# BFMC_Powerboard_v0_2.net
KiCad netlist of a schematic drawn in EAGLE
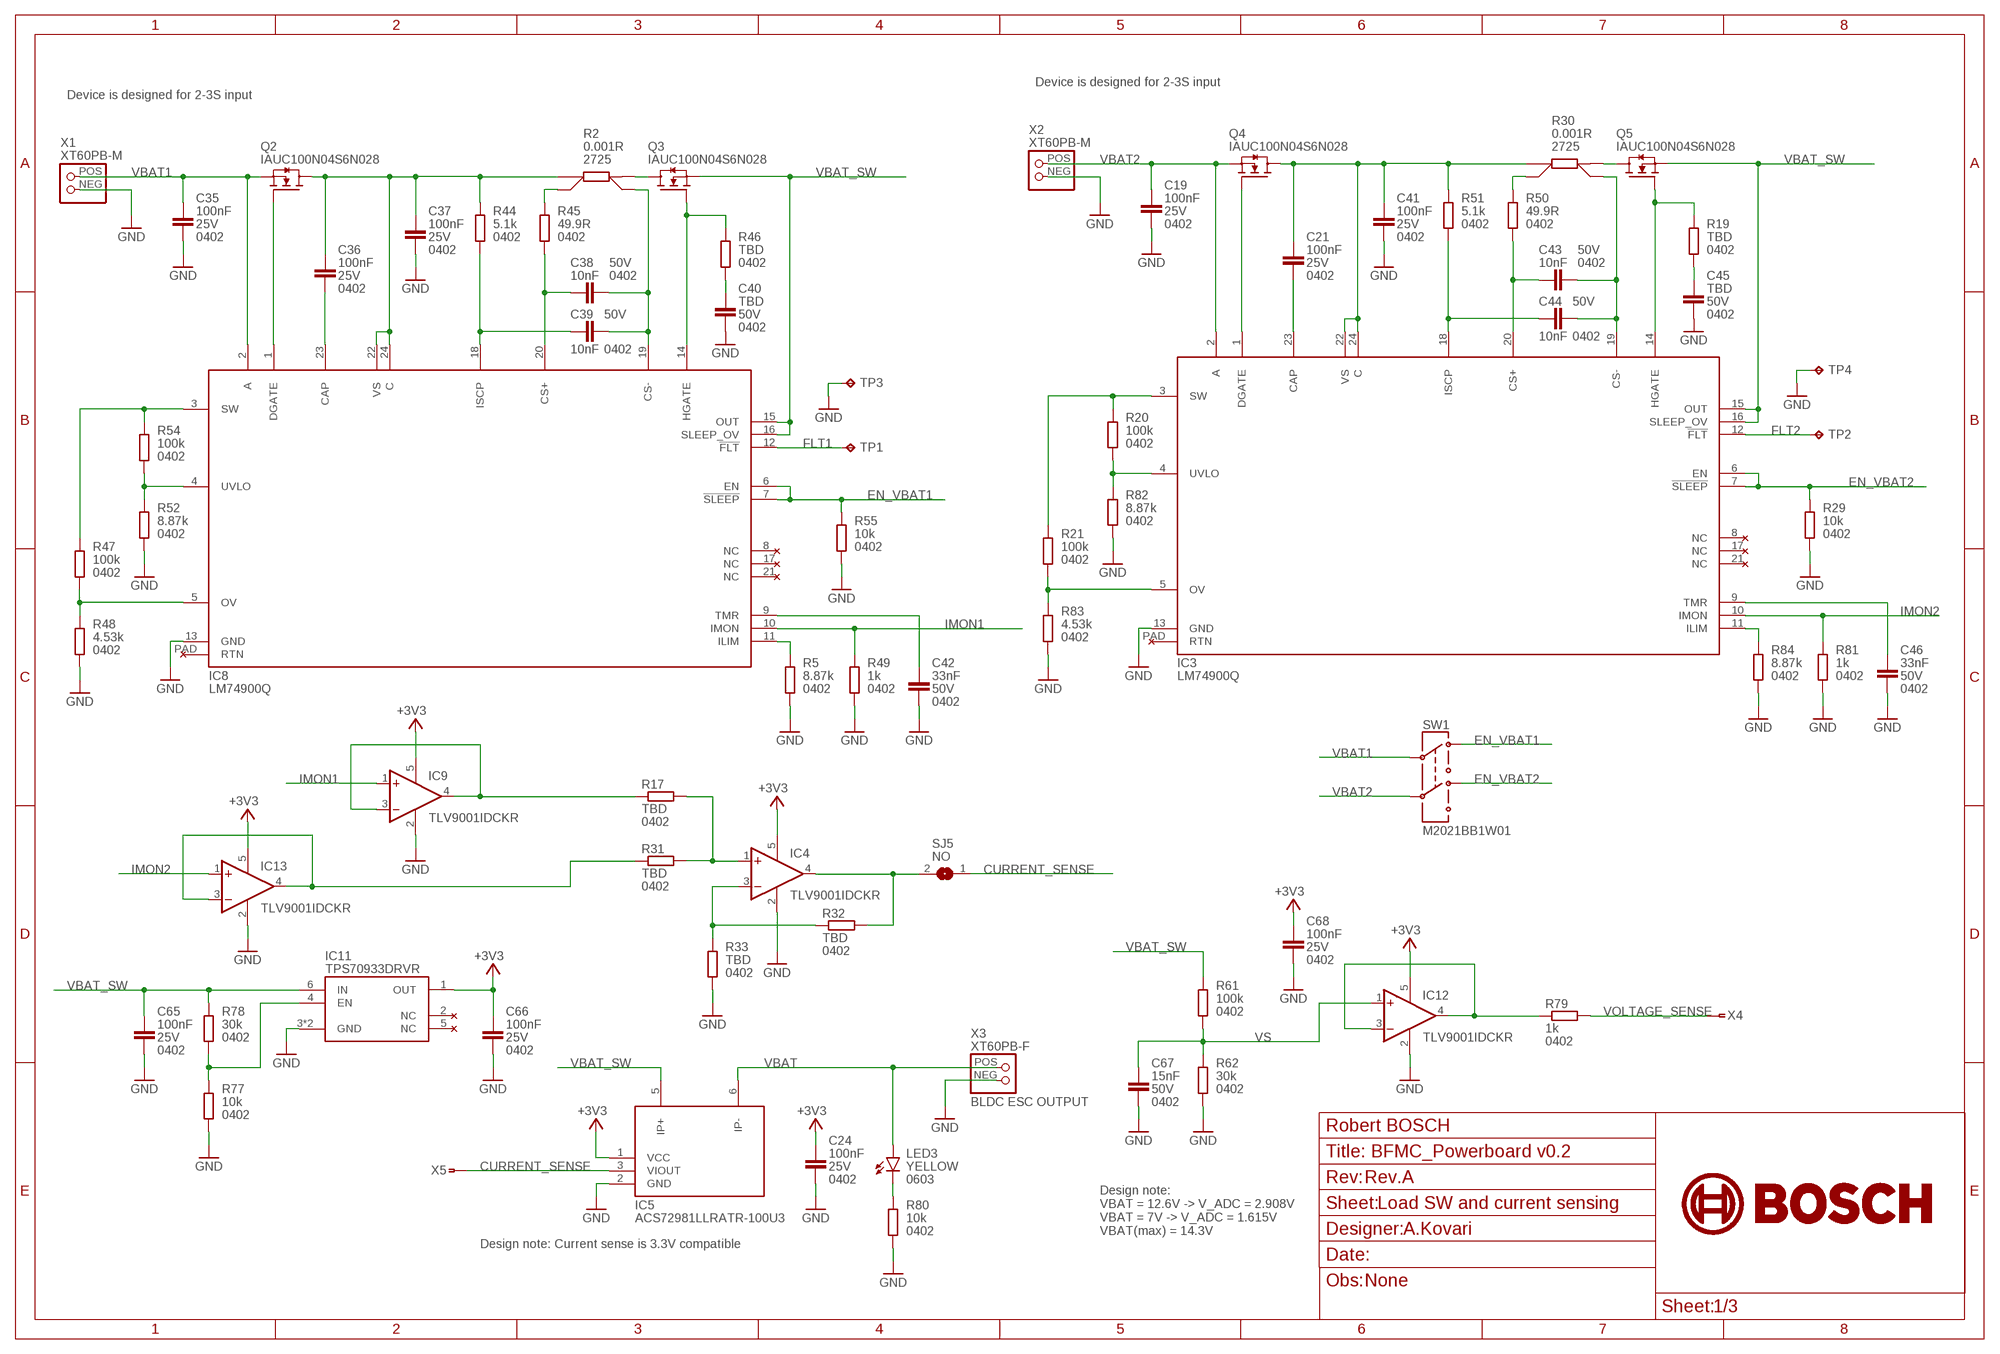
[diagram p0: schematic, sheet 1]
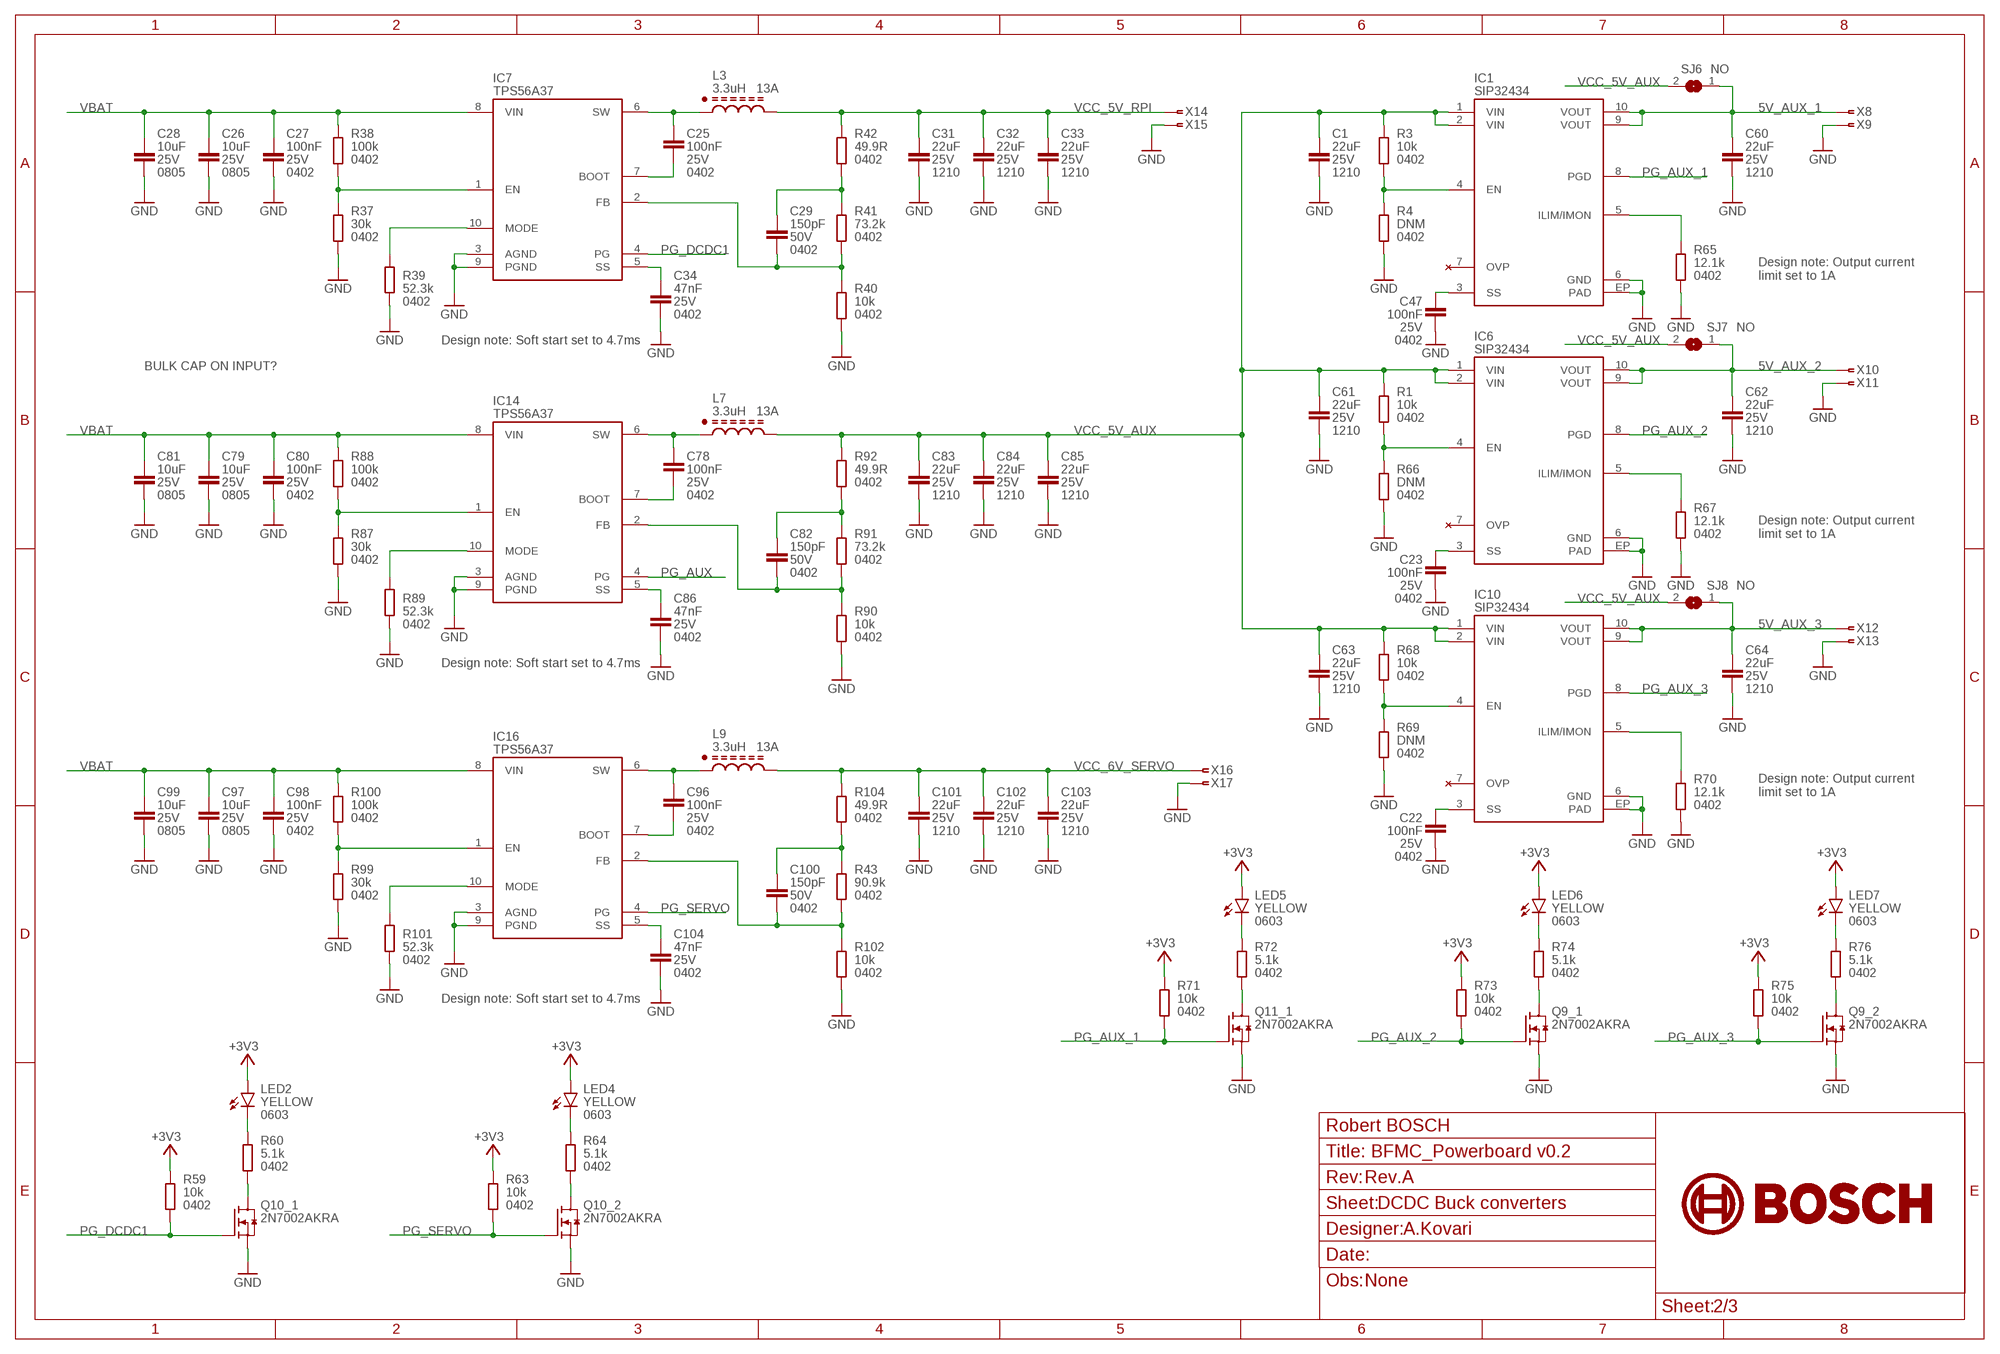
[diagram p1: schematic, sheet 2]
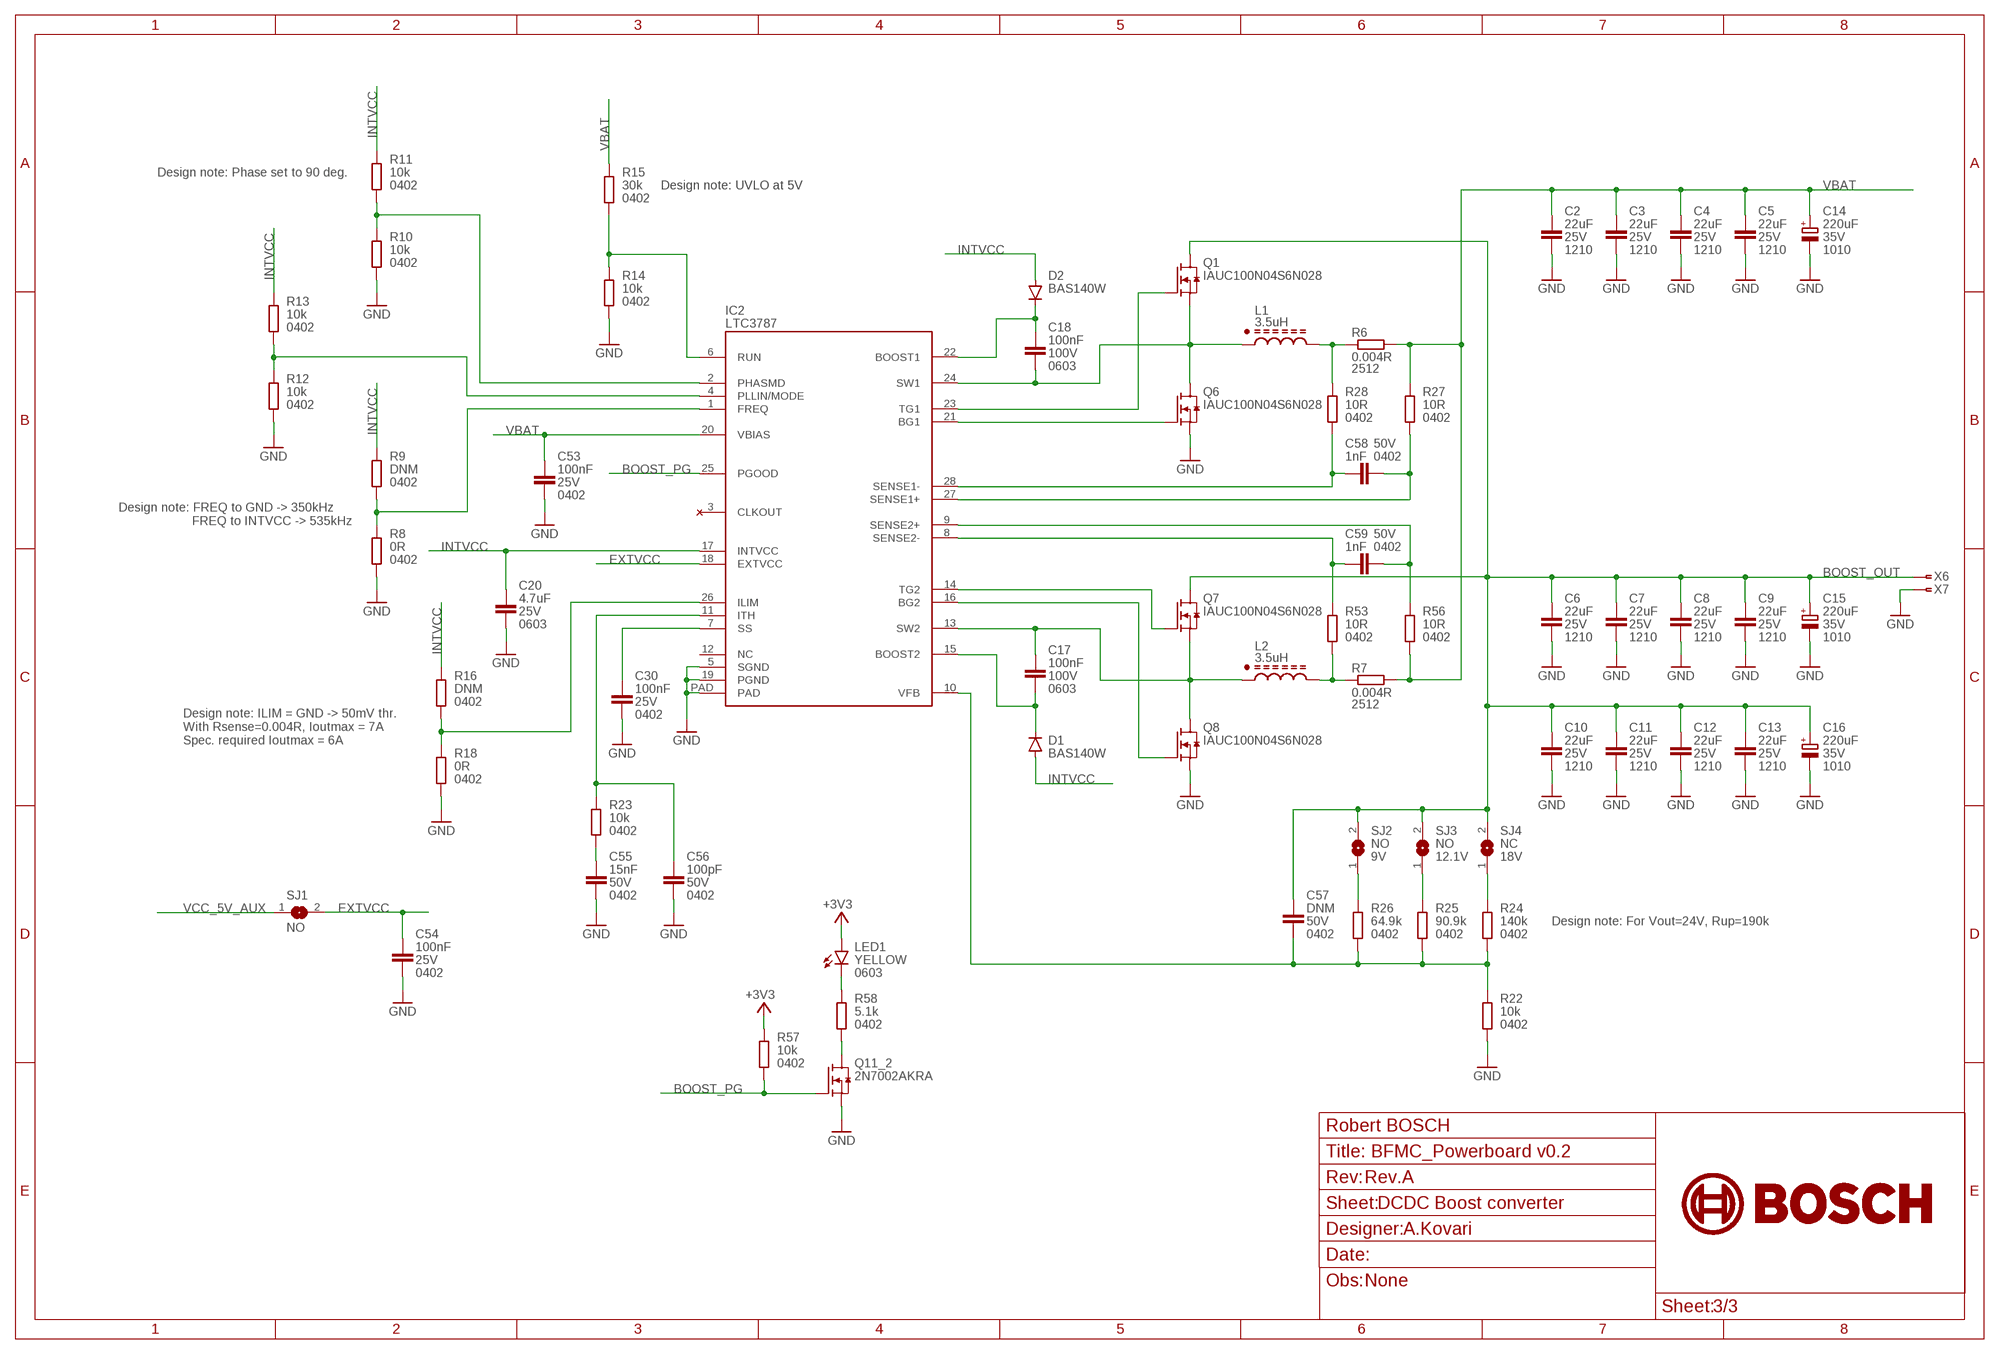
[diagram p2: schematic, sheet 3]

(export (version "E")
  (design (tool "Eeschema 10.0.6"))
  (components
    (comp (ref "C19")
      (value "100nF")
      (footprint "eagle-import:C0402_IPC")
      (fields
        (field (name "VOLTAGE") "25V")
        (field (name "PACKAGE") "0402")
        (field (name "MPN") "CL05B104KA5NNNC")
      )
      (libsource (lib "eagle-import") (part "CL05B104KA5NNNC"))
    )
    (comp (ref "C21")
      (value "100nF")
      (footprint "eagle-import:C0402_IPC")
      (fields
        (field (name "VOLTAGE") "25V")
        (field (name "PACKAGE") "0402")
        (field (name "MPN") "CL05B104KA5NNNC")
      )
      (libsource (lib "eagle-import") (part "CL05B104KA5NNNC"))
    )
    (comp (ref "C24")
      (value "100nF")
      (footprint "eagle-import:C0402_IPC")
      (fields
        (field (name "VOLTAGE") "25V")
        (field (name "PACKAGE") "0402")
        (field (name "MPN") "CL05B104KA5NNNC")
      )
      (libsource (lib "eagle-import") (part "CL05B104KA5NNNC"))
    )
    (comp (ref "C35")
      (value "100nF")
      (footprint "eagle-import:C0402_IPC")
      (fields
        (field (name "VOLTAGE") "25V")
        (field (name "PACKAGE") "0402")
        (field (name "MPN") "CL05B104KA5NNNC")
      )
      (libsource (lib "eagle-import") (part "CL05B104KA5NNNC"))
    )
    (comp (ref "C36")
      (value "100nF")
      (footprint "eagle-import:C0402_IPC")
      (fields
        (field (name "VOLTAGE") "25V")
        (field (name "PACKAGE") "0402")
        (field (name "MPN") "CL05B104KA5NNNC")
      )
      (libsource (lib "eagle-import") (part "CL05B104KA5NNNC"))
    )
    (comp (ref "C37")
      (value "100nF")
      (footprint "eagle-import:C0402_IPC")
      (fields
        (field (name "VOLTAGE") "25V")
        (field (name "PACKAGE") "0402")
        (field (name "MPN") "CL05B104KA5NNNC")
      )
      (libsource (lib "eagle-import") (part "CL05B104KA5NNNC"))
    )
    (comp (ref "C38")
      (value "10nF")
      (footprint "eagle-import:C0402_IPC")
      (fields
        (field (name "VOLTAGE") "50V")
        (field (name "PACKAGE") "0402")
        (field (name "MPN") "GCM155R71H103KA55D")
      )
      (libsource (lib "eagle-import") (part "GCM155R71H103KA55D"))
    )
    (comp (ref "C39")
      (value "10nF")
      (footprint "eagle-import:C0402_IPC")
      (fields
        (field (name "VOLTAGE") "50V")
        (field (name "PACKAGE") "0402")
        (field (name "MPN") "GCM155R71H103KA55D")
      )
      (libsource (lib "eagle-import") (part "GCM155R71H103KA55D"))
    )
    (comp (ref "C40")
      (value "TBD")
      (footprint "eagle-import:C0402_IPC")
      (fields
        (field (name "VOLTAGE") "50V")
        (field (name "PACKAGE") "0402")
        (field (name "MPN") "GCM155R71H103KA55D")
      )
      (libsource (lib "eagle-import") (part "GCM155R71H103KA55D"))
    )
    (comp (ref "C41")
      (value "100nF")
      (footprint "eagle-import:C0402_IPC")
      (fields
        (field (name "VOLTAGE") "25V")
        (field (name "PACKAGE") "0402")
        (field (name "MPN") "CL05B104KA5NNNC")
      )
      (libsource (lib "eagle-import") (part "CL05B104KA5NNNC"))
    )
    (comp (ref "C42")
      (value "33nF")
      (footprint "eagle-import:C0402_IPC")
      (fields
        (field (name "VOLTAGE") "50V")
        (field (name "PACKAGE") "0402")
        (field (name "MPN") "CGA2B3X7R1H333K050BB")
      )
      (libsource (lib "eagle-import") (part "CGA2B3X7R1H333K050BB"))
    )
    (comp (ref "C43")
      (value "10nF")
      (footprint "eagle-import:C0402_IPC")
      (fields
        (field (name "VOLTAGE") "50V")
        (field (name "PACKAGE") "0402")
        (field (name "MPN") "GCM155R71H103KA55D")
      )
      (libsource (lib "eagle-import") (part "GCM155R71H103KA55D"))
    )
    (comp (ref "C44")
      (value "10nF")
      (footprint "eagle-import:C0402_IPC")
      (fields
        (field (name "VOLTAGE") "50V")
        (field (name "PACKAGE") "0402")
        (field (name "MPN") "GCM155R71H103KA55D")
      )
      (libsource (lib "eagle-import") (part "GCM155R71H103KA55D"))
    )
    (comp (ref "C45")
      (value "TBD")
      (footprint "eagle-import:C0402_IPC")
      (fields
        (field (name "VOLTAGE") "50V")
        (field (name "PACKAGE") "0402")
        (field (name "MPN") "GCM155R71H103KA55D")
      )
      (libsource (lib "eagle-import") (part "GCM155R71H103KA55D"))
    )
    (comp (ref "C46")
      (value "33nF")
      (footprint "eagle-import:C0402_IPC")
      (fields
        (field (name "VOLTAGE") "50V")
        (field (name "PACKAGE") "0402")
        (field (name "MPN") "CGA2B3X7R1H333K050BB")
      )
      (libsource (lib "eagle-import") (part "CGA2B3X7R1H333K050BB"))
    )
    (comp (ref "C65")
      (value "100nF")
      (footprint "eagle-import:C0402_IPC")
      (fields
        (field (name "VOLTAGE") "25V")
        (field (name "PACKAGE") "0402")
        (field (name "MPN") "CL05B104KA5NNNC")
      )
      (libsource (lib "eagle-import") (part "CL05B104KA5NNNC"))
    )
    (comp (ref "C66")
      (value "100nF")
      (footprint "eagle-import:C0402_IPC")
      (fields
        (field (name "VOLTAGE") "25V")
        (field (name "PACKAGE") "0402")
        (field (name "MPN") "CL05B104KA5NNNC")
      )
      (libsource (lib "eagle-import") (part "CL05B104KA5NNNC"))
    )
    (comp (ref "C67")
      (value "15nF")
      (footprint "eagle-import:C0402_IPC")
      (fields
        (field (name "VOLTAGE") "50V")
        (field (name "PACKAGE") "0402")
        (field (name "MPN") "GRM155R71H153KA12J")
      )
      (libsource (lib "eagle-import") (part "GRM155R71H153KA12J"))
    )
    (comp (ref "C68")
      (value "100nF")
      (footprint "eagle-import:C0402_IPC")
      (fields
        (field (name "VOLTAGE") "25V")
        (field (name "PACKAGE") "0402")
        (field (name "MPN") "CL05B104KA5NNNC")
      )
      (libsource (lib "eagle-import") (part "CL05B104KA5NNNC"))
    )
    (comp (ref "IC3")
      (value "LM74900Q")
      (footprint "eagle-import:QFN24-4X4")
      (fields (field (name "MPN") " LM74900QRGERQ1"))
      (libsource (lib "eagle-import") (part "LM74900Q"))
    )
    (comp (ref "IC4")
      (value "TLV9001IDCKR")
      (footprint "eagle-import:SC70-5")
      (fields (field (name "MPN") "TLV9001SIDCKR "))
      (libsource (lib "eagle-import") (part "TLV9001IDCKR"))
    )
    (comp (ref "IC5")
      (value "ACS72981LLRATR-100U3")
      (footprint "eagle-import:ACS72981")
      (libsource (lib "eagle-import") (part "ACS72981LLRATR-100U3"))
    )
    (comp (ref "IC8")
      (value "LM74900Q")
      (footprint "eagle-import:QFN24-4X4")
      (fields (field (name "MPN") " LM74900QRGERQ1"))
      (libsource (lib "eagle-import") (part "LM74900Q"))
    )
    (comp (ref "IC9")
      (value "TLV9001IDCKR")
      (footprint "eagle-import:SC70-5")
      (fields (field (name "MPN") "TLV9001SIDCKR "))
      (libsource (lib "eagle-import") (part "TLV9001IDCKR"))
    )
    (comp (ref "IC11")
      (value "TPS70933DRVR")
      (footprint "eagle-import:WSON6_2X2MM_NO_SILK")
      (libsource (lib "eagle-import") (part "TPS70933DRVR"))
    )
    (comp (ref "IC12")
      (value "TLV9001IDCKR")
      (footprint "eagle-import:SC70-5")
      (fields (field (name "MPN") "TLV9001SIDCKR "))
      (libsource (lib "eagle-import") (part "TLV9001IDCKR"))
    )
    (comp (ref "IC13")
      (value "TLV9001IDCKR")
      (footprint "eagle-import:SC70-5")
      (fields (field (name "MPN") "TLV9001SIDCKR "))
      (libsource (lib "eagle-import") (part "TLV9001IDCKR"))
    )
    (comp (ref "LED3")
      (value "YELLOW")
      (footprint "eagle-import:CHIPLED_0603")
      (fields (field (name "PACKAGE") "0603") (field (name "MPN") "150060YS75000"))
      (libsource (lib "eagle-import") (part "150060YS75000"))
    )
    (comp (ref "Q2")
      (value "IAUC100N04S6N028")
      (footprint "eagle-import:PG-TDSON-8")
      (fields (field (name "MPN") " IAUC100N04S6N028"))
      (libsource (lib "eagle-import") (part "IAUC100N04S6N028ATMA1"))
    )
    (comp (ref "Q3")
      (value "IAUC100N04S6N028")
      (footprint "eagle-import:PG-TDSON-8")
      (fields (field (name "MPN") " IAUC100N04S6N028"))
      (libsource (lib "eagle-import") (part "IAUC100N04S6N028ATMA1"))
    )
    (comp (ref "Q4")
      (value "IAUC100N04S6N028")
      (footprint "eagle-import:PG-TDSON-8")
      (fields (field (name "MPN") " IAUC100N04S6N028"))
      (libsource (lib "eagle-import") (part "IAUC100N04S6N028ATMA1"))
    )
    (comp (ref "Q5")
      (value "IAUC100N04S6N028")
      (footprint "eagle-import:PG-TDSON-8")
      (fields (field (name "MPN") " IAUC100N04S6N028"))
      (libsource (lib "eagle-import") (part "IAUC100N04S6N028ATMA1"))
    )
    (comp (ref "R2")
      (value "0.001R")
      (footprint "eagle-import:CRS272")
      (fields (field (name "MPN") "CST272FK-13-R001AA ") (field (name "PACKAGE") "2725"))
      (libsource (lib "eagle-import") (part "CST272FK-13-R001AA"))
    )
    (comp (ref "R5")
      (value "8.87k")
      (footprint "eagle-import:R0402_IPC")
      (fields (field (name "PACKAGE") "0402") (field (name "MPN") "RC0402FR-078K87L"))
      (libsource (lib "eagle-import") (part "RC0402FR-078K87L"))
    )
    (comp (ref "R17")
      (value "TBD")
      (footprint "eagle-import:R0402_IPC")
      (fields (field (name "PACKAGE") "0402") (field (name "MPN") "RC0402FR-131KL"))
      (libsource (lib "eagle-import") (part "RC0402FR-131KL"))
    )
    (comp (ref "R19")
      (value "TBD")
      (footprint "eagle-import:R0402_IPC")
      (fields (field (name "PACKAGE") "0402") (field (name "MPN") "RC0402FR-1349R9L"))
      (libsource (lib "eagle-import") (part "RC0402FR-1349R9L"))
    )
    (comp (ref "R20")
      (value "100k")
      (footprint "eagle-import:R0402_IPC")
      (fields (field (name "PACKAGE") "0402") (field (name "MPN") "RC0402FR-13100KL"))
      (libsource (lib "eagle-import") (part "RC0402FR-13100KL"))
    )
    (comp (ref "R21")
      (value "100k")
      (footprint "eagle-import:R0402_IPC")
      (fields (field (name "PACKAGE") "0402") (field (name "MPN") "RC0402FR-13100KL"))
      (libsource (lib "eagle-import") (part "RC0402FR-13100KL"))
    )
    (comp (ref "R29")
      (value "10k")
      (footprint "eagle-import:R0402_IPC")
      (fields (field (name "PACKAGE") "0402") (field (name "MPN") "RC0402FR-1310KL"))
      (libsource (lib "eagle-import") (part "RC0402FR-1310KL"))
    )
    (comp (ref "R30")
      (value "0.001R")
      (footprint "eagle-import:CRS272")
      (fields (field (name "MPN") "CST272FK-13-R001AA ") (field (name "PACKAGE") "2725"))
      (libsource (lib "eagle-import") (part "CST272FK-13-R001AA"))
    )
    (comp (ref "R31")
      (value "TBD")
      (footprint "eagle-import:R0402_IPC")
      (fields (field (name "PACKAGE") "0402") (field (name "MPN") "RC0402FR-131KL"))
      (libsource (lib "eagle-import") (part "RC0402FR-131KL"))
    )
    (comp (ref "R32")
      (value "TBD")
      (footprint "eagle-import:R0402_IPC")
      (fields (field (name "PACKAGE") "0402") (field (name "MPN") "RC0402FR-131KL"))
      (libsource (lib "eagle-import") (part "RC0402FR-131KL"))
    )
    (comp (ref "R33")
      (value "TBD")
      (footprint "eagle-import:R0402_IPC")
      (fields (field (name "PACKAGE") "0402") (field (name "MPN") "RC0402FR-131KL"))
      (libsource (lib "eagle-import") (part "RC0402FR-131KL"))
    )
    (comp (ref "R44")
      (value "5.1k")
      (footprint "eagle-import:R0402_IPC")
      (fields (field (name "PACKAGE") "0402") (field (name "MPN") "RC0402FR-135K1L"))
      (libsource (lib "eagle-import") (part "RC0402FR-135K1L"))
    )
    (comp (ref "R45")
      (value "49.9R")
      (footprint "eagle-import:R0402_IPC")
      (fields (field (name "PACKAGE") "0402") (field (name "MPN") "RC0402FR-1349R9L"))
      (libsource (lib "eagle-import") (part "RC0402FR-1349R9L"))
    )
    (comp (ref "R46")
      (value "TBD")
      (footprint "eagle-import:R0402_IPC")
      (fields (field (name "PACKAGE") "0402") (field (name "MPN") "RC0402FR-1349R9L"))
      (libsource (lib "eagle-import") (part "RC0402FR-1349R9L"))
    )
    (comp (ref "R47")
      (value "100k")
      (footprint "eagle-import:R0402_IPC")
      (fields (field (name "PACKAGE") "0402") (field (name "MPN") "RC0402FR-13100KL"))
      (libsource (lib "eagle-import") (part "RC0402FR-13100KL"))
    )
    (comp (ref "R48")
      (value "4.53k")
      (footprint "eagle-import:R0402_IPC")
      (fields (field (name "PACKAGE") "0402") (field (name "MPN") "RC0402FR-074K53L"))
      (libsource (lib "eagle-import") (part "RC0402FR-074K53L"))
    )
    (comp (ref "R49")
      (value "1k")
      (footprint "eagle-import:R0402_IPC")
      (fields (field (name "PACKAGE") "0402") (field (name "MPN") "RC0402FR-131KL"))
      (libsource (lib "eagle-import") (part "RC0402FR-131KL"))
    )
    (comp (ref "R50")
      (value "49.9R")
      (footprint "eagle-import:R0402_IPC")
      (fields (field (name "PACKAGE") "0402") (field (name "MPN") "RC0402FR-1349R9L"))
      (libsource (lib "eagle-import") (part "RC0402FR-1349R9L"))
    )
    (comp (ref "R51")
      (value "5.1k")
      (footprint "eagle-import:R0402_IPC")
      (fields (field (name "PACKAGE") "0402") (field (name "MPN") "RC0402FR-135K1L"))
      (libsource (lib "eagle-import") (part "RC0402FR-135K1L"))
    )
    (comp (ref "R52")
      (value "8.87k")
      (footprint "eagle-import:R0402_IPC")
      (fields (field (name "PACKAGE") "0402") (field (name "MPN") "RC0402FR-078K87L"))
      (libsource (lib "eagle-import") (part "RC0402FR-078K87L"))
    )
    (comp (ref "R54")
      (value "100k")
      (footprint "eagle-import:R0402_IPC")
      (fields (field (name "PACKAGE") "0402") (field (name "MPN") "RC0402FR-13100KL"))
      (libsource (lib "eagle-import") (part "RC0402FR-13100KL"))
    )
    (comp (ref "R55")
      (value "10k")
      (footprint "eagle-import:R0402_IPC")
      (fields (field (name "PACKAGE") "0402") (field (name "MPN") "RC0402FR-1310KL"))
      (libsource (lib "eagle-import") (part "RC0402FR-1310KL"))
    )
    (comp (ref "R61")
      (value "100k")
      (footprint "eagle-import:R0402_IPC")
      (fields (field (name "PACKAGE") "0402") (field (name "MPN") "RC0402FR-13100KL"))
      (libsource (lib "eagle-import") (part "RC0402FR-13100KL"))
    )
    (comp (ref "R62")
      (value "30k")
      (footprint "eagle-import:R0402_IPC")
      (fields (field (name "PACKAGE") "0402") (field (name "MPN") "RC0402FR-1330KL"))
      (libsource (lib "eagle-import") (part "RC0402FR-1330KL"))
    )
    (comp (ref "R77")
      (value "10k")
      (footprint "eagle-import:R0402_IPC")
      (fields (field (name "PACKAGE") "0402") (field (name "MPN") "RC0402FR-1310KL"))
      (libsource (lib "eagle-import") (part "RC0402FR-1310KL"))
    )
    (comp (ref "R78")
      (value "30k")
      (footprint "eagle-import:R0402_IPC")
      (fields (field (name "PACKAGE") "0402") (field (name "MPN") "RC0402FR-1330KL"))
      (libsource (lib "eagle-import") (part "RC0402FR-1330KL"))
    )
    (comp (ref "R79")
      (value "1k")
      (footprint "eagle-import:R0402_IPC")
      (fields (field (name "PACKAGE") "0402") (field (name "MPN") "RC0402FR-131KL"))
      (libsource (lib "eagle-import") (part "RC0402FR-131KL"))
    )
    (comp (ref "R80")
      (value "10k")
      (footprint "eagle-import:R0402_IPC")
      (fields (field (name "PACKAGE") "0402") (field (name "MPN") "RC0402FR-1310KL"))
      (libsource (lib "eagle-import") (part "RC0402FR-1310KL"))
    )
    (comp (ref "R81")
      (value "1k")
      (footprint "eagle-import:R0402_IPC")
      (fields (field (name "PACKAGE") "0402") (field (name "MPN") "RC0402FR-131KL"))
      (libsource (lib "eagle-import") (part "RC0402FR-131KL"))
    )
    (comp (ref "R82")
      (value "8.87k")
      (footprint "eagle-import:R0402_IPC")
      (fields (field (name "PACKAGE") "0402") (field (name "MPN") "RC0402FR-078K87L"))
      (libsource (lib "eagle-import") (part "RC0402FR-078K87L"))
    )
    (comp (ref "R83")
      (value "4.53k")
      (footprint "eagle-import:R0402_IPC")
      (fields (field (name "PACKAGE") "0402") (field (name "MPN") "RC0402FR-074K53L"))
      (libsource (lib "eagle-import") (part "RC0402FR-074K53L"))
    )
    (comp (ref "R84")
      (value "8.87k")
      (footprint "eagle-import:R0402_IPC")
      (fields (field (name "PACKAGE") "0402") (field (name "MPN") "RC0402FR-078K87L"))
      (libsource (lib "eagle-import") (part "RC0402FR-078K87L"))
    )
    (comp (ref "SJ5")
      (value "NO")
      (footprint "eagle-import:SJ_1X1.5_NO")
      (libsource (lib "eagle-import") (part "SJ_1.5X1_NO"))
    )
    (comp (ref "SW1")
      (value "M2021BB1W01")
      (footprint "eagle-import:M2021BB1W01")
      (libsource (lib "eagle-import") (part "M2021BB1W01"))
    )
    (comp (ref "TP1")
      (value "TPTP13R")
      (footprint "eagle-import:TP13R")
      (libsource (lib "eagle-import") (part "TPTP13R"))
    )
    (comp (ref "TP2")
      (value "TPTP13R")
      (footprint "eagle-import:TP13R")
      (libsource (lib "eagle-import") (part "TPTP13R"))
    )
    (comp (ref "TP3")
      (value "TPTP13R")
      (footprint "eagle-import:TP13R")
      (libsource (lib "eagle-import") (part "TPTP13R"))
    )
    (comp (ref "TP4")
      (value "TPTP13R")
      (footprint "eagle-import:TP13R")
      (libsource (lib "eagle-import") (part "TPTP13R"))
    )
    (comp (ref "X1")
      (value "XT60PB-M")
      (footprint "eagle-import:XT60PB")
      (libsource (lib "eagle-import") (part "XT60PB-M"))
    )
    (comp (ref "X2")
      (value "XT60PB-M")
      (footprint "eagle-import:XT60PB")
      (libsource (lib "eagle-import") (part "XT60PB-M"))
    )
    (comp (ref "X3")
      (value "XT60PB-F")
      (footprint "eagle-import:XT60PB")
      (libsource (lib "eagle-import") (part "XT60PB-F"))
    )
    (comp (ref "X4")
      (value "ZFKDSA1-W-6,35")
      (footprint "eagle-import:1704994")
      (fields (field (name "MPN") "1704994"))
      (libsource (lib "eagle-import") (part "ZFKDSA1-W-6,35"))
    )
    (comp (ref "X5")
      (value "ZFKDSA1-W-6,35")
      (footprint "eagle-import:1704994")
      (fields (field (name "MPN") "1704994"))
      (libsource (lib "eagle-import") (part "ZFKDSA1-W-6,35"))
    )
    (comp (ref "C1")
      (value "22uF")
      (footprint "eagle-import:C1210")
      (fields
        (field (name "PACKAGE") "1210")
        (field (name "VOLTAGE") "25V")
        (field (name "MPN") "CL32A226KAJNNNE")
      )
      (libsource (lib "eagle-import") (part "CL32A226KAJNNNE"))
    )
    (comp (ref "C22")
      (value "100nF")
      (footprint "eagle-import:C0402_IPC")
      (fields
        (field (name "VOLTAGE") "25V")
        (field (name "PACKAGE") "0402")
        (field (name "MPN") "CL05B104KA5NNNC")
      )
      (libsource (lib "eagle-import") (part "CL05B104KA5NNNC"))
    )
    (comp (ref "C23")
      (value "100nF")
      (footprint "eagle-import:C0402_IPC")
      (fields
        (field (name "VOLTAGE") "25V")
        (field (name "PACKAGE") "0402")
        (field (name "MPN") "CL05B104KA5NNNC")
      )
      (libsource (lib "eagle-import") (part "CL05B104KA5NNNC"))
    )
    (comp (ref "C25")
      (value "100nF")
      (footprint "eagle-import:C0402_IPC")
      (fields
        (field (name "VOLTAGE") "25V")
        (field (name "PACKAGE") "0402")
        (field (name "MPN") "CL05B104KA5NNNC")
      )
      (libsource (lib "eagle-import") (part "CL05B104KA5NNNC"))
    )
    (comp (ref "C26")
      (value "10uF")
      (footprint "eagle-import:C0805")
      (fields
        (field (name "PACKAGE") "0805")
        (field (name "VOLTAGE") "25V")
        (field (name "MPN") "GRM21BR61E106KA73K")
      )
      (libsource (lib "eagle-import") (part "GRM21BR61E106KA73K"))
    )
    (comp (ref "C27")
      (value "100nF")
      (footprint "eagle-import:C0402_IPC")
      (fields
        (field (name "VOLTAGE") "25V")
        (field (name "PACKAGE") "0402")
        (field (name "MPN") "CL05B104KA5NNNC")
      )
      (libsource (lib "eagle-import") (part "CL05B104KA5NNNC"))
    )
    (comp (ref "C28")
      (value "10uF")
      (footprint "eagle-import:C0805")
      (fields
        (field (name "PACKAGE") "0805")
        (field (name "VOLTAGE") "25V")
        (field (name "MPN") "GRM21BR61E106KA73K")
      )
      (libsource (lib "eagle-import") (part "GRM21BR61E106KA73K"))
    )
    (comp (ref "C29")
      (value "150pF")
      (footprint "eagle-import:C0402_IPC")
      (fields
        (field (name "VOLTAGE") "50V")
        (field (name "PACKAGE") "0402")
        (field (name "MPN") "GCM1555C1H151JA16J")
      )
      (libsource (lib "eagle-import") (part "GCM1555C1H151JA16J"))
    )
    (comp (ref "C31")
      (value "22uF")
      (footprint "eagle-import:C1210")
      (fields
        (field (name "PACKAGE") "1210")
        (field (name "VOLTAGE") "25V")
        (field (name "MPN") "CL32A226KAJNNNE")
      )
      (libsource (lib "eagle-import") (part "CL32A226KAJNNNE"))
    )
    (comp (ref "C32")
      (value "22uF")
      (footprint "eagle-import:C1210")
      (fields
        (field (name "PACKAGE") "1210")
        (field (name "VOLTAGE") "25V")
        (field (name "MPN") "CL32A226KAJNNNE")
      )
      (libsource (lib "eagle-import") (part "CL32A226KAJNNNE"))
    )
    (comp (ref "C33")
      (value "22uF")
      (footprint "eagle-import:C1210")
      (fields
        (field (name "PACKAGE") "1210")
        (field (name "VOLTAGE") "25V")
        (field (name "MPN") "CL32A226KAJNNNE")
      )
      (libsource (lib "eagle-import") (part "CL32A226KAJNNNE"))
    )
    (comp (ref "C34")
      (value "47nF")
      (footprint "eagle-import:C0402_IPC")
      (fields
        (field (name "VOLTAGE") "25V")
        (field (name "PACKAGE") "0402")
        (field (name "MPN") "CL05B473KA5NNNC")
      )
      (libsource (lib "eagle-import") (part "CL05B473KA5NNNC"))
    )
    (comp (ref "C47")
      (value "100nF")
      (footprint "eagle-import:C0402_IPC")
      (fields
        (field (name "VOLTAGE") "25V")
        (field (name "PACKAGE") "0402")
        (field (name "MPN") "CL05B104KA5NNNC")
      )
      (libsource (lib "eagle-import") (part "CL05B104KA5NNNC"))
    )
    (comp (ref "C60")
      (value "22uF")
      (footprint "eagle-import:C1210")
      (fields
        (field (name "PACKAGE") "1210")
        (field (name "VOLTAGE") "25V")
        (field (name "MPN") "CL32A226KAJNNNE")
      )
      (libsource (lib "eagle-import") (part "CL32A226KAJNNNE"))
    )
    (comp (ref "C61")
      (value "22uF")
      (footprint "eagle-import:C1210")
      (fields
        (field (name "PACKAGE") "1210")
        (field (name "VOLTAGE") "25V")
        (field (name "MPN") "CL32A226KAJNNNE")
      )
      (libsource (lib "eagle-import") (part "CL32A226KAJNNNE"))
    )
    (comp (ref "C62")
      (value "22uF")
      (footprint "eagle-import:C1210")
      (fields
        (field (name "PACKAGE") "1210")
        (field (name "VOLTAGE") "25V")
        (field (name "MPN") "CL32A226KAJNNNE")
      )
      (libsource (lib "eagle-import") (part "CL32A226KAJNNNE"))
    )
    (comp (ref "C63")
      (value "22uF")
      (footprint "eagle-import:C1210")
      (fields
        (field (name "PACKAGE") "1210")
        (field (name "VOLTAGE") "25V")
        (field (name "MPN") "CL32A226KAJNNNE")
      )
      (libsource (lib "eagle-import") (part "CL32A226KAJNNNE"))
    )
    (comp (ref "C64")
      (value "22uF")
      (footprint "eagle-import:C1210")
      (fields
        (field (name "PACKAGE") "1210")
        (field (name "VOLTAGE") "25V")
        (field (name "MPN") "CL32A226KAJNNNE")
      )
      (libsource (lib "eagle-import") (part "CL32A226KAJNNNE"))
    )
    (comp (ref "C78")
      (value "100nF")
      (footprint "eagle-import:C0402_IPC")
      (fields
        (field (name "VOLTAGE") "25V")
        (field (name "PACKAGE") "0402")
        (field (name "MPN") "CL05B104KA5NNNC")
      )
      (libsource (lib "eagle-import") (part "CL05B104KA5NNNC"))
    )
    (comp (ref "C79")
      (value "10uF")
      (footprint "eagle-import:C0805")
      (fields
        (field (name "PACKAGE") "0805")
        (field (name "VOLTAGE") "25V")
        (field (name "MPN") "GRM21BR61E106KA73K")
      )
      (libsource (lib "eagle-import") (part "GRM21BR61E106KA73K"))
    )
    (comp (ref "C80")
      (value "100nF")
      (footprint "eagle-import:C0402_IPC")
      (fields
        (field (name "VOLTAGE") "25V")
        (field (name "PACKAGE") "0402")
        (field (name "MPN") "CL05B104KA5NNNC")
      )
      (libsource (lib "eagle-import") (part "CL05B104KA5NNNC"))
    )
    (comp (ref "C81")
      (value "10uF")
      (footprint "eagle-import:C0805")
      (fields
        (field (name "PACKAGE") "0805")
        (field (name "VOLTAGE") "25V")
        (field (name "MPN") "GRM21BR61E106KA73K")
      )
      (libsource (lib "eagle-import") (part "GRM21BR61E106KA73K"))
    )
    (comp (ref "C82")
      (value "150pF")
      (footprint "eagle-import:C0402_IPC")
      (fields
        (field (name "VOLTAGE") "50V")
        (field (name "PACKAGE") "0402")
        (field (name "MPN") "GCM1555C1H151JA16J")
      )
      (libsource (lib "eagle-import") (part "GCM1555C1H151JA16J"))
    )
    (comp (ref "C83")
      (value "22uF")
      (footprint "eagle-import:C1210")
      (fields
        (field (name "PACKAGE") "1210")
        (field (name "VOLTAGE") "25V")
        (field (name "MPN") "CL32A226KAJNNNE")
      )
      (libsource (lib "eagle-import") (part "CL32A226KAJNNNE"))
    )
    (comp (ref "C84")
      (value "22uF")
      (footprint "eagle-import:C1210")
      (fields
        (field (name "PACKAGE") "1210")
        (field (name "VOLTAGE") "25V")
        (field (name "MPN") "CL32A226KAJNNNE")
      )
      (libsource (lib "eagle-import") (part "CL32A226KAJNNNE"))
    )
    (comp (ref "C85")
      (value "22uF")
      (footprint "eagle-import:C1210")
      (fields
        (field (name "PACKAGE") "1210")
        (field (name "VOLTAGE") "25V")
        (field (name "MPN") "CL32A226KAJNNNE")
      )
      (libsource (lib "eagle-import") (part "CL32A226KAJNNNE"))
    )
    (comp (ref "C86")
      (value "47nF")
      (footprint "eagle-import:C0402_IPC")
      (fields
        (field (name "VOLTAGE") "25V")
        (field (name "PACKAGE") "0402")
        (field (name "MPN") "CL05B473KA5NNNC")
      )
      (libsource (lib "eagle-import") (part "CL05B473KA5NNNC"))
    )
    (comp (ref "C96")
      (value "100nF")
      (footprint "eagle-import:C0402_IPC")
      (fields
        (field (name "VOLTAGE") "25V")
        (field (name "PACKAGE") "0402")
        (field (name "MPN") "CL05B104KA5NNNC")
      )
      (libsource (lib "eagle-import") (part "CL05B104KA5NNNC"))
    )
    (comp (ref "C97")
      (value "10uF")
      (footprint "eagle-import:C0805")
      (fields
        (field (name "PACKAGE") "0805")
        (field (name "VOLTAGE") "25V")
        (field (name "MPN") "GRM21BR61E106KA73K")
      )
      (libsource (lib "eagle-import") (part "GRM21BR61E106KA73K"))
    )
    (comp (ref "C98")
      (value "100nF")
      (footprint "eagle-import:C0402_IPC")
      (fields
        (field (name "VOLTAGE") "25V")
        (field (name "PACKAGE") "0402")
        (field (name "MPN") "CL05B104KA5NNNC")
      )
      (libsource (lib "eagle-import") (part "CL05B104KA5NNNC"))
    )
    (comp (ref "C99")
      (value "10uF")
      (footprint "eagle-import:C0805")
      (fields
        (field (name "PACKAGE") "0805")
        (field (name "VOLTAGE") "25V")
        (field (name "MPN") "GRM21BR61E106KA73K")
      )
      (libsource (lib "eagle-import") (part "GRM21BR61E106KA73K"))
    )
    (comp (ref "C100")
      (value "150pF")
      (footprint "eagle-import:C0402_IPC")
      (fields
        (field (name "VOLTAGE") "50V")
        (field (name "PACKAGE") "0402")
        (field (name "MPN") "GCM1555C1H151JA16J")
      )
      (libsource (lib "eagle-import") (part "GCM1555C1H151JA16J"))
    )
    (comp (ref "C101")
      (value "22uF")
      (footprint "eagle-import:C1210")
      (fields
        (field (name "PACKAGE") "1210")
        (field (name "VOLTAGE") "25V")
        (field (name "MPN") "CL32A226KAJNNNE")
      )
      (libsource (lib "eagle-import") (part "CL32A226KAJNNNE"))
    )
    (comp (ref "C102")
      (value "22uF")
      (footprint "eagle-import:C1210")
      (fields
        (field (name "PACKAGE") "1210")
        (field (name "VOLTAGE") "25V")
        (field (name "MPN") "CL32A226KAJNNNE")
      )
      (libsource (lib "eagle-import") (part "CL32A226KAJNNNE"))
    )
    (comp (ref "C103")
      (value "22uF")
      (footprint "eagle-import:C1210")
      (fields
        (field (name "PACKAGE") "1210")
        (field (name "VOLTAGE") "25V")
        (field (name "MPN") "CL32A226KAJNNNE")
      )
      (libsource (lib "eagle-import") (part "CL32A226KAJNNNE"))
    )
    (comp (ref "C104")
      (value "47nF")
      (footprint "eagle-import:C0402_IPC")
      (fields
        (field (name "VOLTAGE") "25V")
        (field (name "PACKAGE") "0402")
        (field (name "MPN") "CL05B473KA5NNNC")
      )
      (libsource (lib "eagle-import") (part "CL05B473KA5NNNC"))
    )
    (comp (ref "IC1")
      (value "SIP32434")
      (footprint "eagle-import:DFN10-3X3")
      (fields (field (name "MPN") "SIP32434ADN-T1E4"))
      (libsource (lib "eagle-import") (part "SIP32434"))
    )
    (comp (ref "IC6")
      (value "SIP32434")
      (footprint "eagle-import:DFN10-3X3")
      (fields (field (name "MPN") "SIP32434ADN-T1E4"))
      (libsource (lib "eagle-import") (part "SIP32434"))
    )
    (comp (ref "IC7")
      (value "TPS56A37")
      (footprint "eagle-import:VQFN-HR-RPA")
      (fields (field (name "MPN") "TPS56A37RPAR"))
      (libsource (lib "eagle-import") (part "TPS56A37"))
    )
    (comp (ref "IC10")
      (value "SIP32434")
      (footprint "eagle-import:DFN10-3X3")
      (fields (field (name "MPN") "SIP32434ADN-T1E4"))
      (libsource (lib "eagle-import") (part "SIP32434"))
    )
    (comp (ref "IC14")
      (value "TPS56A37")
      (footprint "eagle-import:VQFN-HR-RPA")
      (fields (field (name "MPN") "TPS56A37RPAR"))
      (libsource (lib "eagle-import") (part "TPS56A37"))
    )
    (comp (ref "IC16")
      (value "TPS56A37")
      (footprint "eagle-import:VQFN-HR-RPA")
      (fields (field (name "MPN") "TPS56A37RPAR"))
      (libsource (lib "eagle-import") (part "TPS56A37"))
    )
    (comp (ref "L3")
      (value "3.3uH")
      (footprint "eagle-import:EXLA1V0705")
      (fields (field (name "MPN") "EXLA1V0705-3R3-R") (field (name "CURRENT") "13A"))
      (libsource (lib "eagle-import") (part "EXLA1V0705-3R3-R"))
    )
    (comp (ref "L7")
      (value "3.3uH")
      (footprint "eagle-import:EXLA1V0705")
      (fields (field (name "MPN") "EXLA1V0705-3R3-R") (field (name "CURRENT") "13A"))
      (libsource (lib "eagle-import") (part "EXLA1V0705-3R3-R"))
    )
    (comp (ref "L9")
      (value "3.3uH")
      (footprint "eagle-import:EXLA1V0705")
      (fields (field (name "MPN") "EXLA1V0705-3R3-R") (field (name "CURRENT") "13A"))
      (libsource (lib "eagle-import") (part "EXLA1V0705-3R3-R"))
    )
    (comp (ref "LED2")
      (value "YELLOW")
      (footprint "eagle-import:CHIPLED_0603")
      (fields (field (name "PACKAGE") "0603") (field (name "MPN") "150060YS75000"))
      (libsource (lib "eagle-import") (part "150060YS75000"))
    )
    (comp (ref "LED4")
      (value "YELLOW")
      (footprint "eagle-import:CHIPLED_0603")
      (fields (field (name "PACKAGE") "0603") (field (name "MPN") "150060YS75000"))
      (libsource (lib "eagle-import") (part "150060YS75000"))
    )
    (comp (ref "LED5")
      (value "YELLOW")
      (footprint "eagle-import:CHIPLED_0603")
      (fields (field (name "PACKAGE") "0603") (field (name "MPN") "150060YS75000"))
      (libsource (lib "eagle-import") (part "150060YS75000"))
    )
    (comp (ref "LED6")
      (value "YELLOW")
      (footprint "eagle-import:CHIPLED_0603")
      (fields (field (name "PACKAGE") "0603") (field (name "MPN") "150060YS75000"))
      (libsource (lib "eagle-import") (part "150060YS75000"))
    )
    (comp (ref "LED7")
      (value "YELLOW")
      (footprint "eagle-import:CHIPLED_0603")
      (fields (field (name "PACKAGE") "0603") (field (name "MPN") "150060YS75000"))
      (libsource (lib "eagle-import") (part "150060YS75000"))
    )
    (comp (ref "Q9")
      (value "2N7002AKRA")
      (footprint "eagle-import:DFN1412-6")
      (fields (field (name "MPN") "2N7002AKRA-QZ"))
      (libsource (lib "eagle-import") (part "2N7002AKRA"))
    )
    (comp (ref "Q10")
      (value "2N7002AKRA")
      (footprint "eagle-import:DFN1412-6")
      (fields (field (name "MPN") "2N7002AKRA-QZ"))
      (libsource (lib "eagle-import") (part "2N7002AKRA"))
    )
    (comp (ref "Q11")
      (value "2N7002AKRA")
      (footprint "eagle-import:DFN1412-6")
      (fields (field (name "MPN") "2N7002AKRA-QZ"))
      (libsource (lib "eagle-import") (part "2N7002AKRA"))
    )
    (comp (ref "R1")
      (value "10k")
      (footprint "eagle-import:R0402_IPC")
      (fields (field (name "PACKAGE") "0402") (field (name "MPN") "RC0402FR-1310KL"))
      (libsource (lib "eagle-import") (part "RC0402FR-1310KL"))
    )
    (comp (ref "R3")
      (value "10k")
      (footprint "eagle-import:R0402_IPC")
      (fields (field (name "PACKAGE") "0402") (field (name "MPN") "RC0402FR-1310KL"))
      (libsource (lib "eagle-import") (part "RC0402FR-1310KL"))
    )
    (comp (ref "R4")
      (value "DNM")
      (footprint "eagle-import:R0402_IPC")
      (fields (field (name "PACKAGE") "0402") (field (name "MPN") "RC0402FR-1310KL"))
      (libsource (lib "eagle-import") (part "RC0402FR-1310KL"))
    )
    (comp (ref "R37")
      (value "30k")
      (footprint "eagle-import:R0402_IPC")
      (fields (field (name "PACKAGE") "0402") (field (name "MPN") "RC0402FR-1330KL"))
      (libsource (lib "eagle-import") (part "RC0402FR-1330KL"))
    )
    (comp (ref "R38")
      (value "100k")
      (footprint "eagle-import:R0402_IPC")
      (fields (field (name "PACKAGE") "0402") (field (name "MPN") "RC0402FR-13100KL"))
      (libsource (lib "eagle-import") (part "RC0402FR-13100KL"))
    )
    (comp (ref "R39")
      (value "52.3k")
      (footprint "eagle-import:R0402_IPC")
      (fields (field (name "PACKAGE") "0402") (field (name "MPN") "RC0402FR-1352K3L"))
      (libsource (lib "eagle-import") (part "RC0402FR-1352K3L"))
    )
    (comp (ref "R40")
      (value "10k")
      (footprint "eagle-import:R0402_IPC")
      (fields (field (name "PACKAGE") "0402") (field (name "MPN") "RC0402FR-1310KL"))
      (libsource (lib "eagle-import") (part "RC0402FR-1310KL"))
    )
    (comp (ref "R41")
      (value "73.2k")
      (footprint "eagle-import:R0402_IPC")
      (fields (field (name "PACKAGE") "0402") (field (name "MPN") "RC0402FR-1373K2L"))
      (libsource (lib "eagle-import") (part "RC0402FR-1373K2L"))
    )
    (comp (ref "R42")
      (value "49.9R")
      (footprint "eagle-import:R0402_IPC")
      (fields (field (name "PACKAGE") "0402") (field (name "MPN") "RC0402FR-1349R9L"))
      (libsource (lib "eagle-import") (part "RC0402FR-1349R9L"))
    )
    (comp (ref "R43")
      (value "90.9k")
      (footprint "eagle-import:R0402_IPC")
      (fields (field (name "PACKAGE") "0402") (field (name "MPN") "RC0402FR-0790K9L"))
      (libsource (lib "eagle-import") (part "RC0402FR-0790K9L"))
    )
    (comp (ref "R59")
      (value "10k")
      (footprint "eagle-import:R0402_IPC")
      (fields (field (name "PACKAGE") "0402") (field (name "MPN") "RC0402FR-1310KL"))
      (libsource (lib "eagle-import") (part "RC0402FR-1310KL"))
    )
    (comp (ref "R60")
      (value "5.1k")
      (footprint "eagle-import:R0402_IPC")
      (fields (field (name "PACKAGE") "0402") (field (name "MPN") "RC0402FR-135K1L"))
      (libsource (lib "eagle-import") (part "RC0402FR-135K1L"))
    )
    (comp (ref "R63")
      (value "10k")
      (footprint "eagle-import:R0402_IPC")
      (fields (field (name "PACKAGE") "0402") (field (name "MPN") "RC0402FR-1310KL"))
      (libsource (lib "eagle-import") (part "RC0402FR-1310KL"))
    )
    (comp (ref "R64")
      (value "5.1k")
      (footprint "eagle-import:R0402_IPC")
      (fields (field (name "PACKAGE") "0402") (field (name "MPN") "RC0402FR-135K1L"))
      (libsource (lib "eagle-import") (part "RC0402FR-135K1L"))
    )
    (comp (ref "R65")
      (value "12.1k")
      (footprint "eagle-import:R0402_IPC")
      (fields (field (name "PACKAGE") "0402") (field (name "MPN") "RC0402FR-0712K1L"))
      (libsource (lib "eagle-import") (part "RC0402FR-0712K1L"))
    )
    (comp (ref "R66")
      (value "DNM")
      (footprint "eagle-import:R0402_IPC")
      (fields (field (name "PACKAGE") "0402") (field (name "MPN") "RC0402FR-1310KL"))
      (libsource (lib "eagle-import") (part "RC0402FR-1310KL"))
    )
    (comp (ref "R67")
      (value "12.1k")
      (footprint "eagle-import:R0402_IPC")
      (fields (field (name "PACKAGE") "0402") (field (name "MPN") "RC0402FR-0712K1L"))
      (libsource (lib "eagle-import") (part "RC0402FR-0712K1L"))
    )
    (comp (ref "R68")
      (value "10k")
      (footprint "eagle-import:R0402_IPC")
      (fields (field (name "PACKAGE") "0402") (field (name "MPN") "RC0402FR-1310KL"))
      (libsource (lib "eagle-import") (part "RC0402FR-1310KL"))
    )
    (comp (ref "R69")
      (value "DNM")
      (footprint "eagle-import:R0402_IPC")
      (fields (field (name "PACKAGE") "0402") (field (name "MPN") "RC0402FR-1310KL"))
      (libsource (lib "eagle-import") (part "RC0402FR-1310KL"))
    )
    (comp (ref "R70")
      (value "12.1k")
      (footprint "eagle-import:R0402_IPC")
      (fields (field (name "PACKAGE") "0402") (field (name "MPN") "RC0402FR-0712K1L"))
      (libsource (lib "eagle-import") (part "RC0402FR-0712K1L"))
    )
    (comp (ref "R71")
      (value "10k")
      (footprint "eagle-import:R0402_IPC")
      (fields (field (name "PACKAGE") "0402") (field (name "MPN") "RC0402FR-1310KL"))
      (libsource (lib "eagle-import") (part "RC0402FR-1310KL"))
    )
    (comp (ref "R72")
      (value "5.1k")
      (footprint "eagle-import:R0402_IPC")
      (fields (field (name "PACKAGE") "0402") (field (name "MPN") "RC0402FR-135K1L"))
      (libsource (lib "eagle-import") (part "RC0402FR-135K1L"))
    )
    (comp (ref "R73")
      (value "10k")
      (footprint "eagle-import:R0402_IPC")
      (fields (field (name "PACKAGE") "0402") (field (name "MPN") "RC0402FR-1310KL"))
      (libsource (lib "eagle-import") (part "RC0402FR-1310KL"))
    )
    (comp (ref "R74")
      (value "5.1k")
      (footprint "eagle-import:R0402_IPC")
      (fields (field (name "PACKAGE") "0402") (field (name "MPN") "RC0402FR-135K1L"))
      (libsource (lib "eagle-import") (part "RC0402FR-135K1L"))
    )
    (comp (ref "R75")
      (value "10k")
      (footprint "eagle-import:R0402_IPC")
      (fields (field (name "PACKAGE") "0402") (field (name "MPN") "RC0402FR-1310KL"))
      (libsource (lib "eagle-import") (part "RC0402FR-1310KL"))
    )
    (comp (ref "R76")
      (value "5.1k")
      (footprint "eagle-import:R0402_IPC")
      (fields (field (name "PACKAGE") "0402") (field (name "MPN") "RC0402FR-135K1L"))
      (libsource (lib "eagle-import") (part "RC0402FR-135K1L"))
    )
    (comp (ref "R87")
      (value "30k")
      (footprint "eagle-import:R0402_IPC")
      (fields (field (name "PACKAGE") "0402") (field (name "MPN") "RC0402FR-1330KL"))
      (libsource (lib "eagle-import") (part "RC0402FR-1330KL"))
    )
    (comp (ref "R88")
      (value "100k")
      (footprint "eagle-import:R0402_IPC")
      (fields (field (name "PACKAGE") "0402") (field (name "MPN") "RC0402FR-13100KL"))
      (libsource (lib "eagle-import") (part "RC0402FR-13100KL"))
    )
    (comp (ref "R89")
      (value "52.3k")
      (footprint "eagle-import:R0402_IPC")
      (fields (field (name "PACKAGE") "0402") (field (name "MPN") "RC0402FR-1352K3L"))
      (libsource (lib "eagle-import") (part "RC0402FR-1352K3L"))
    )
    (comp (ref "R90")
      (value "10k")
      (footprint "eagle-import:R0402_IPC")
      (fields (field (name "PACKAGE") "0402") (field (name "MPN") "RC0402FR-1310KL"))
      (libsource (lib "eagle-import") (part "RC0402FR-1310KL"))
    )
    (comp (ref "R91")
      (value "73.2k")
      (footprint "eagle-import:R0402_IPC")
      (fields (field (name "PACKAGE") "0402") (field (name "MPN") "RC0402FR-1373K2L"))
      (libsource (lib "eagle-import") (part "RC0402FR-1373K2L"))
    )
    (comp (ref "R92")
      (value "49.9R")
      (footprint "eagle-import:R0402_IPC")
      (fields (field (name "PACKAGE") "0402") (field (name "MPN") "RC0402FR-1349R9L"))
      (libsource (lib "eagle-import") (part "RC0402FR-1349R9L"))
    )
    (comp (ref "R99")
      (value "30k")
      (footprint "eagle-import:R0402_IPC")
      (fields (field (name "PACKAGE") "0402") (field (name "MPN") "RC0402FR-1330KL"))
      (libsource (lib "eagle-import") (part "RC0402FR-1330KL"))
    )
    (comp (ref "R100")
      (value "100k")
      (footprint "eagle-import:R0402_IPC")
      (fields (field (name "PACKAGE") "0402") (field (name "MPN") "RC0402FR-13100KL"))
      (libsource (lib "eagle-import") (part "RC0402FR-13100KL"))
    )
    (comp (ref "R101")
      (value "52.3k")
      (footprint "eagle-import:R0402_IPC")
      (fields (field (name "PACKAGE") "0402") (field (name "MPN") "RC0402FR-1352K3L"))
      (libsource (lib "eagle-import") (part "RC0402FR-1352K3L"))
    )
    (comp (ref "R102")
      (value "10k")
      (footprint "eagle-import:R0402_IPC")
      (fields (field (name "PACKAGE") "0402") (field (name "MPN") "RC0402FR-1310KL"))
      (libsource (lib "eagle-import") (part "RC0402FR-1310KL"))
    )
    (comp (ref "R104")
      (value "49.9R")
      (footprint "eagle-import:R0402_IPC")
      (fields (field (name "PACKAGE") "0402") (field (name "MPN") "RC0402FR-1349R9L"))
      (libsource (lib "eagle-import") (part "RC0402FR-1349R9L"))
    )
    (comp (ref "SJ6")
      (value "NO")
      (footprint "eagle-import:SJ_1X1.5_NO")
      (libsource (lib "eagle-import") (part "SJ_1.5X1_NO"))
    )
    (comp (ref "SJ7")
      (value "NO")
      (footprint "eagle-import:SJ_1X1.5_NO")
      (libsource (lib "eagle-import") (part "SJ_1.5X1_NO"))
    )
    (comp (ref "SJ8")
      (value "NO")
      (footprint "eagle-import:SJ_1X1.5_NO")
      (libsource (lib "eagle-import") (part "SJ_1.5X1_NO"))
    )
    (comp (ref "X8")
      (value "ZFKDSA1-W-6,35")
      (footprint "eagle-import:1704994")
      (fields (field (name "MPN") "1704994"))
      (libsource (lib "eagle-import") (part "ZFKDSA1-W-6,35"))
    )
    (comp (ref "X9")
      (value "ZFKDSA1-W-6,35")
      (footprint "eagle-import:1704994")
      (fields (field (name "MPN") "1704994"))
      (libsource (lib "eagle-import") (part "ZFKDSA1-W-6,35"))
    )
    (comp (ref "X10")
      (value "ZFKDSA1-W-6,35")
      (footprint "eagle-import:1704994")
      (fields (field (name "MPN") "1704994"))
      (libsource (lib "eagle-import") (part "ZFKDSA1-W-6,35"))
    )
    (comp (ref "X11")
      (value "ZFKDSA1-W-6,35")
      (footprint "eagle-import:1704994")
      (fields (field (name "MPN") "1704994"))
      (libsource (lib "eagle-import") (part "ZFKDSA1-W-6,35"))
    )
    (comp (ref "X12")
      (value "ZFKDSA1-W-6,35")
      (footprint "eagle-import:1704994")
      (fields (field (name "MPN") "1704994"))
      (libsource (lib "eagle-import") (part "ZFKDSA1-W-6,35"))
    )
    (comp (ref "X13")
      (value "ZFKDSA1-W-6,35")
      (footprint "eagle-import:1704994")
      (fields (field (name "MPN") "1704994"))
      (libsource (lib "eagle-import") (part "ZFKDSA1-W-6,35"))
    )
    (comp (ref "X14")
      (value "ZFKDSA1-W-6,35")
      (footprint "eagle-import:1704994")
      (fields (field (name "MPN") "1704994"))
      (libsource (lib "eagle-import") (part "ZFKDSA1-W-6,35"))
    )
    (comp (ref "X15")
      (value "ZFKDSA1-W-6,35")
      (footprint "eagle-import:1704994")
      (fields (field (name "MPN") "1704994"))
      (libsource (lib "eagle-import") (part "ZFKDSA1-W-6,35"))
    )
    (comp (ref "X16")
      (value "ZFKDSA1-W-6,35")
      (footprint "eagle-import:1704994")
      (fields (field (name "MPN") "1704994"))
      (libsource (lib "eagle-import") (part "ZFKDSA1-W-6,35"))
    )
    (comp (ref "X17")
      (value "ZFKDSA1-W-6,35")
      (footprint "eagle-import:1704994")
      (fields (field (name "MPN") "1704994"))
      (libsource (lib "eagle-import") (part "ZFKDSA1-W-6,35"))
    )
    (comp (ref "C2")
      (value "22uF")
      (footprint "eagle-import:C1210")
      (fields
        (field (name "PACKAGE") "1210")
        (field (name "VOLTAGE") "25V")
        (field (name "MPN") "CL32A226KAJNNNE")
      )
      (libsource (lib "eagle-import") (part "CL32A226KAJNNNE"))
    )
    (comp (ref "C3")
      (value "22uF")
      (footprint "eagle-import:C1210")
      (fields
        (field (name "PACKAGE") "1210")
        (field (name "VOLTAGE") "25V")
        (field (name "MPN") "CL32A226KAJNNNE")
      )
      (libsource (lib "eagle-import") (part "CL32A226KAJNNNE"))
    )
    (comp (ref "C4")
      (value "22uF")
      (footprint "eagle-import:C1210")
      (fields
        (field (name "PACKAGE") "1210")
        (field (name "VOLTAGE") "25V")
        (field (name "MPN") "CL32A226KAJNNNE")
      )
      (libsource (lib "eagle-import") (part "CL32A226KAJNNNE"))
    )
    (comp (ref "C5")
      (value "22uF")
      (footprint "eagle-import:C1210")
      (fields
        (field (name "PACKAGE") "1210")
        (field (name "VOLTAGE") "25V")
        (field (name "MPN") "CL32A226KAJNNNE")
      )
      (libsource (lib "eagle-import") (part "CL32A226KAJNNNE"))
    )
    (comp (ref "C6")
      (value "22uF")
      (footprint "eagle-import:C1210")
      (fields
        (field (name "PACKAGE") "1210")
        (field (name "VOLTAGE") "25V")
        (field (name "MPN") "CL32A226KAJNNNE")
      )
      (libsource (lib "eagle-import") (part "CL32A226KAJNNNE"))
    )
    (comp (ref "C7")
      (value "22uF")
      (footprint "eagle-import:C1210")
      (fields
        (field (name "PACKAGE") "1210")
        (field (name "VOLTAGE") "25V")
        (field (name "MPN") "CL32A226KAJNNNE")
      )
      (libsource (lib "eagle-import") (part "CL32A226KAJNNNE"))
    )
    (comp (ref "C8")
      (value "22uF")
      (footprint "eagle-import:C1210")
      (fields
        (field (name "PACKAGE") "1210")
        (field (name "VOLTAGE") "25V")
        (field (name "MPN") "CL32A226KAJNNNE")
      )
      (libsource (lib "eagle-import") (part "CL32A226KAJNNNE"))
    )
    (comp (ref "C9")
      (value "22uF")
      (footprint "eagle-import:C1210")
      (fields
        (field (name "PACKAGE") "1210")
        (field (name "VOLTAGE") "25V")
        (field (name "MPN") "CL32A226KAJNNNE")
      )
      (libsource (lib "eagle-import") (part "CL32A226KAJNNNE"))
    )
    (comp (ref "C10")
      (value "22uF")
      (footprint "eagle-import:C1210")
      (fields
        (field (name "PACKAGE") "1210")
        (field (name "VOLTAGE") "25V")
        (field (name "MPN") "CL32A226KAJNNNE")
      )
      (libsource (lib "eagle-import") (part "CL32A226KAJNNNE"))
    )
    (comp (ref "C11")
      (value "22uF")
      (footprint "eagle-import:C1210")
      (fields
        (field (name "PACKAGE") "1210")
        (field (name "VOLTAGE") "25V")
        (field (name "MPN") "CL32A226KAJNNNE")
      )
      (libsource (lib "eagle-import") (part "CL32A226KAJNNNE"))
    )
    (comp (ref "C12")
      (value "22uF")
      (footprint "eagle-import:C1210")
      (fields
        (field (name "PACKAGE") "1210")
        (field (name "VOLTAGE") "25V")
        (field (name "MPN") "CL32A226KAJNNNE")
      )
      (libsource (lib "eagle-import") (part "CL32A226KAJNNNE"))
    )
    (comp (ref "C13")
      (value "22uF")
      (footprint "eagle-import:C1210")
      (fields
        (field (name "PACKAGE") "1210")
        (field (name "VOLTAGE") "25V")
        (field (name "MPN") "CL32A226KAJNNNE")
      )
      (libsource (lib "eagle-import") (part "CL32A226KAJNNNE"))
    )
    (comp (ref "C14")
      (value "220uF")
      (footprint "eagle-import:CAP_POL_1010")
      (fields
        (field (name "VOLTAGE") "35V")
        (field (name "PACKAGE") "1010")
        (field (name "MPN") "865060557008 ")
      )
      (libsource (lib "eagle-import") (part "865060557008"))
    )
    (comp (ref "C15")
      (value "220uF")
      (footprint "eagle-import:CAP_POL_1010")
      (fields
        (field (name "VOLTAGE") "35V")
        (field (name "PACKAGE") "1010")
        (field (name "MPN") "865060557008 ")
      )
      (libsource (lib "eagle-import") (part "865060557008"))
    )
    (comp (ref "C16")
      (value "220uF")
      (footprint "eagle-import:CAP_POL_1010")
      (fields
        (field (name "VOLTAGE") "35V")
        (field (name "PACKAGE") "1010")
        (field (name "MPN") "865060557008 ")
      )
      (libsource (lib "eagle-import") (part "865060557008"))
    )
    (comp (ref "C17")
      (value "100nF")
      (footprint "eagle-import:C0603")
      (fields
        (field (name "PACKAGE") "0603")
        (field (name "VOLTAGE") "100V")
        (field (name "MPN") "CL10B104KC8NNNC")
      )
      (libsource (lib "eagle-import") (part "CL10B104KC8NNNC"))
    )
    (comp (ref "C18")
      (value "100nF")
      (footprint "eagle-import:C0603")
      (fields
        (field (name "PACKAGE") "0603")
        (field (name "VOLTAGE") "100V")
        (field (name "MPN") "CL10B104KC8NNNC")
      )
      (libsource (lib "eagle-import") (part "CL10B104KC8NNNC"))
    )
    (comp (ref "C20")
      (value "4.7uF")
      (footprint "eagle-import:C0603")
      (fields
        (field (name "PACKAGE") "0603")
        (field (name "VOLTAGE") "25V")
        (field (name "MPN") "C1608X5R1E475K080AC")
      )
      (libsource (lib "eagle-import") (part "C1608X5R1E475K080AC"))
    )
    (comp (ref "C30")
      (value "100nF")
      (footprint "eagle-import:C0402_IPC")
      (fields
        (field (name "VOLTAGE") "25V")
        (field (name "PACKAGE") "0402")
        (field (name "MPN") "CL05B104KA5NNNC")
      )
      (libsource (lib "eagle-import") (part "CL05B104KA5NNNC"))
    )
    (comp (ref "C53")
      (value "100nF")
      (footprint "eagle-import:C0402_IPC")
      (fields
        (field (name "VOLTAGE") "25V")
        (field (name "PACKAGE") "0402")
        (field (name "MPN") "CL05B104KA5NNNC")
      )
      (libsource (lib "eagle-import") (part "CL05B104KA5NNNC"))
    )
    (comp (ref "C54")
      (value "100nF")
      (footprint "eagle-import:C0402_IPC")
      (fields
        (field (name "VOLTAGE") "25V")
        (field (name "PACKAGE") "0402")
        (field (name "MPN") "CL05B104KA5NNNC")
      )
      (libsource (lib "eagle-import") (part "CL05B104KA5NNNC"))
    )
    (comp (ref "C55")
      (value "15nF")
      (footprint "eagle-import:C0402_IPC")
      (fields
        (field (name "VOLTAGE") "50V")
        (field (name "PACKAGE") "0402")
        (field (name "MPN") "GRM155R71H153KA12J")
      )
      (libsource (lib "eagle-import") (part "GRM155R71H153KA12J"))
    )
    (comp (ref "C56")
      (value "100pF")
      (footprint "eagle-import:C0402_IPC")
      (fields
        (field (name "VOLTAGE") "50V")
        (field (name "PACKAGE") "0402")
        (field (name "MPN") "GRM1555C1H101JA01D")
      )
      (libsource (lib "eagle-import") (part "GRM1555C1H101JA01D"))
    )
    (comp (ref "C57")
      (value "DNM")
      (footprint "eagle-import:C0402_IPC")
      (fields
        (field (name "VOLTAGE") "50V")
        (field (name "PACKAGE") "0402")
        (field (name "MPN") "GJM1555C1H470FB01D")
      )
      (libsource (lib "eagle-import") (part "GJM1555C1H470FB01D"))
    )
    (comp (ref "C58")
      (value "1nF")
      (footprint "eagle-import:C0402_IPC")
      (fields
        (field (name "VOLTAGE") "50V")
        (field (name "PACKAGE") "0402")
        (field (name "MPN") "GRM1555C1H102JA01D")
      )
      (libsource (lib "eagle-import") (part "GRM1555C1H102JA01D"))
    )
    (comp (ref "C59")
      (value "1nF")
      (footprint "eagle-import:C0402_IPC")
      (fields
        (field (name "VOLTAGE") "50V")
        (field (name "PACKAGE") "0402")
        (field (name "MPN") "GRM1555C1H102JA01D")
      )
      (libsource (lib "eagle-import") (part "GRM1555C1H102JA01D"))
    )
    (comp (ref "D1")
      (value "BAS140W")
      (footprint "eagle-import:SOD323-R")
      (fields (field (name "MPN") "BAS140WE6327HTSA1"))
      (libsource (lib "eagle-import") (part "BAS140WE6327HTSA1"))
    )
    (comp (ref "D2")
      (value "BAS140W")
      (footprint "eagle-import:SOD323-R")
      (fields (field (name "MPN") "BAS140WE6327HTSA1"))
      (libsource (lib "eagle-import") (part "BAS140WE6327HTSA1"))
    )
    (comp (ref "IC2")
      (value "LTC3787")
      (footprint "eagle-import:UFD-QFN28-4X5MM")
      (fields (field (name "MPN") "LTC3787EUFD"))
      (libsource (lib "eagle-import") (part "LTC3787"))
    )
    (comp (ref "L1")
      (value "3.5uH")
      (footprint "eagle-import:7447709003")
      (fields (field (name "MPN") "7447709003"))
      (libsource (lib "eagle-import") (part "7447709003"))
    )
    (comp (ref "L2")
      (value "3.5uH")
      (footprint "eagle-import:7447709003")
      (fields (field (name "MPN") "7447709003"))
      (libsource (lib "eagle-import") (part "7447709003"))
    )
    (comp (ref "LED1")
      (value "YELLOW")
      (footprint "eagle-import:CHIPLED_0603")
      (fields (field (name "PACKAGE") "0603") (field (name "MPN") "150060YS75000"))
      (libsource (lib "eagle-import") (part "150060YS75000"))
    )
    (comp (ref "Q1")
      (value "IAUC100N04S6N028")
      (footprint "eagle-import:PG-TDSON-8")
      (fields (field (name "MPN") " IAUC100N04S6N028"))
      (libsource (lib "eagle-import") (part "IAUC100N04S6N028ATMA1"))
    )
    (comp (ref "Q6")
      (value "IAUC100N04S6N028")
      (footprint "eagle-import:PG-TDSON-8")
      (fields (field (name "MPN") " IAUC100N04S6N028"))
      (libsource (lib "eagle-import") (part "IAUC100N04S6N028ATMA1"))
    )
    (comp (ref "Q7")
      (value "IAUC100N04S6N028")
      (footprint "eagle-import:PG-TDSON-8")
      (fields (field (name "MPN") " IAUC100N04S6N028"))
      (libsource (lib "eagle-import") (part "IAUC100N04S6N028ATMA1"))
    )
    (comp (ref "Q8")
      (value "IAUC100N04S6N028")
      (footprint "eagle-import:PG-TDSON-8")
      (fields (field (name "MPN") " IAUC100N04S6N028"))
      (libsource (lib "eagle-import") (part "IAUC100N04S6N028ATMA1"))
    )
    (comp (ref "R6")
      (value "0.004R")
      (footprint "eagle-import:R2512")
      (fields (field (name "PACKAGE") "2512") (field (name "MPN") "CRF2512-FZ-R004ELF"))
      (libsource (lib "eagle-import") (part "CRF2512-FZ-R004ELF"))
    )
    (comp (ref "R7")
      (value "0.004R")
      (footprint "eagle-import:R2512")
      (fields (field (name "PACKAGE") "2512") (field (name "MPN") "CRF2512-FZ-R004ELF"))
      (libsource (lib "eagle-import") (part "CRF2512-FZ-R004ELF"))
    )
    (comp (ref "R8")
      (value "0R")
      (footprint "eagle-import:R0402_IPC")
      (fields (field (name "PACKAGE") "0402") (field (name "MPN") "RC0402JR-100RL"))
      (libsource (lib "eagle-import") (part "RC0402JR-100RL"))
    )
    (comp (ref "R9")
      (value "DNM")
      (footprint "eagle-import:R0402_IPC")
      (fields (field (name "PACKAGE") "0402") (field (name "MPN") "RC0402JR-100RL"))
      (libsource (lib "eagle-import") (part "RC0402JR-100RL"))
    )
    (comp (ref "R10")
      (value "10k")
      (footprint "eagle-import:R0402_IPC")
      (fields (field (name "PACKAGE") "0402") (field (name "MPN") "RC0402FR-1310KL"))
      (libsource (lib "eagle-import") (part "RC0402FR-1310KL"))
    )
    (comp (ref "R11")
      (value "10k")
      (footprint "eagle-import:R0402_IPC")
      (fields (field (name "PACKAGE") "0402") (field (name "MPN") "RC0402FR-1310KL"))
      (libsource (lib "eagle-import") (part "RC0402FR-1310KL"))
    )
    (comp (ref "R12")
      (value "10k")
      (footprint "eagle-import:R0402_IPC")
      (fields (field (name "PACKAGE") "0402") (field (name "MPN") "RC0402FR-1310KL"))
      (libsource (lib "eagle-import") (part "RC0402FR-1310KL"))
    )
    (comp (ref "R13")
      (value "10k")
      (footprint "eagle-import:R0402_IPC")
      (fields (field (name "PACKAGE") "0402") (field (name "MPN") "RC0402FR-1310KL"))
      (libsource (lib "eagle-import") (part "RC0402FR-1310KL"))
    )
    (comp (ref "R14")
      (value "10k")
      (footprint "eagle-import:R0402_IPC")
      (fields (field (name "PACKAGE") "0402") (field (name "MPN") "RC0402FR-1310KL"))
      (libsource (lib "eagle-import") (part "RC0402FR-1310KL"))
    )
    (comp (ref "R15")
      (value "30k")
      (footprint "eagle-import:R0402_IPC")
      (fields (field (name "PACKAGE") "0402") (field (name "MPN") "RC0402FR-1330KL"))
      (libsource (lib "eagle-import") (part "RC0402FR-1330KL"))
    )
    (comp (ref "R16")
      (value "DNM")
      (footprint "eagle-import:R0402_IPC")
      (fields (field (name "PACKAGE") "0402") (field (name "MPN") "RC0402JR-100RL"))
      (libsource (lib "eagle-import") (part "RC0402JR-100RL"))
    )
    (comp (ref "R18")
      (value "0R")
      (footprint "eagle-import:R0402_IPC")
      (fields (field (name "PACKAGE") "0402") (field (name "MPN") "RC0402JR-100RL"))
      (libsource (lib "eagle-import") (part "RC0402JR-100RL"))
    )
    (comp (ref "R22")
      (value "10k")
      (footprint "eagle-import:R0402_IPC")
      (fields (field (name "PACKAGE") "0402") (field (name "MPN") "RC0402FR-1310KL"))
      (libsource (lib "eagle-import") (part "RC0402FR-1310KL"))
    )
    (comp (ref "R23")
      (value "10k")
      (footprint "eagle-import:R0402_IPC")
      (fields (field (name "PACKAGE") "0402") (field (name "MPN") "RC0402FR-1310KL"))
      (libsource (lib "eagle-import") (part "RC0402FR-1310KL"))
    )
    (comp (ref "R24")
      (value "140k")
      (footprint "eagle-import:R0402_IPC")
      (fields (field (name "PACKAGE") "0402") (field (name "MPN") "RC0402FR-13140KL"))
      (libsource (lib "eagle-import") (part "RC0402FR-13140KL"))
    )
    (comp (ref "R25")
      (value "90.9k")
      (footprint "eagle-import:R0402_IPC")
      (fields (field (name "PACKAGE") "0402") (field (name "MPN") "RC0402FR-0790K9L"))
      (libsource (lib "eagle-import") (part "RC0402FR-0790K9L"))
    )
    (comp (ref "R26")
      (value "64.9k")
      (footprint "eagle-import:R0402_IPC")
      (fields (field (name "PACKAGE") "0402") (field (name "MPN") "RC0402FR-1364K9L"))
      (libsource (lib "eagle-import") (part "RC0402FR-1364K9L"))
    )
    (comp (ref "R27")
      (value "10R")
      (footprint "eagle-import:R0402_IPC")
      (fields (field (name "PACKAGE") "0402") (field (name "MPN") "RC0402FR-1310RL"))
      (libsource (lib "eagle-import") (part "RC0402FR-1310RL"))
    )
    (comp (ref "R28")
      (value "10R")
      (footprint "eagle-import:R0402_IPC")
      (fields (field (name "PACKAGE") "0402") (field (name "MPN") "RC0402FR-1310RL"))
      (libsource (lib "eagle-import") (part "RC0402FR-1310RL"))
    )
    (comp (ref "R53")
      (value "10R")
      (footprint "eagle-import:R0402_IPC")
      (fields (field (name "PACKAGE") "0402") (field (name "MPN") "RC0402FR-1310RL"))
      (libsource (lib "eagle-import") (part "RC0402FR-1310RL"))
    )
    (comp (ref "R56")
      (value "10R")
      (footprint "eagle-import:R0402_IPC")
      (fields (field (name "PACKAGE") "0402") (field (name "MPN") "RC0402FR-1310RL"))
      (libsource (lib "eagle-import") (part "RC0402FR-1310RL"))
    )
    (comp (ref "R57")
      (value "10k")
      (footprint "eagle-import:R0402_IPC")
      (fields (field (name "PACKAGE") "0402") (field (name "MPN") "RC0402FR-1310KL"))
      (libsource (lib "eagle-import") (part "RC0402FR-1310KL"))
    )
    (comp (ref "R58")
      (value "5.1k")
      (footprint "eagle-import:R0402_IPC")
      (fields (field (name "PACKAGE") "0402") (field (name "MPN") "RC0402FR-135K1L"))
      (libsource (lib "eagle-import") (part "RC0402FR-135K1L"))
    )
    (comp (ref "SJ1")
      (value "NO")
      (footprint "eagle-import:SJ_1X1.5_NO")
      (libsource (lib "eagle-import") (part "SJ_1.5X1_NO"))
    )
    (comp (ref "SJ2")
      (value "NO")
      (footprint "eagle-import:SJ_1X1.5_NO")
      (libsource (lib "eagle-import") (part "SJ_1.5X1_NO"))
    )
    (comp (ref "SJ3")
      (value "NO")
      (footprint "eagle-import:SJ_1X1.5_NO")
      (libsource (lib "eagle-import") (part "SJ_1.5X1_NO"))
    )
    (comp (ref "SJ4")
      (value "NC")
      (footprint "eagle-import:SJ_1X1.5_NO")
      (libsource (lib "eagle-import") (part "SJ_1.5X1_NO"))
    )
    (comp (ref "X6")
      (value "ZFKDSA1-W-6,35")
      (footprint "eagle-import:1704994")
      (fields (field (name "MPN") "1704994"))
      (libsource (lib "eagle-import") (part "ZFKDSA1-W-6,35"))
    )
    (comp (ref "X7")
      (value "ZFKDSA1-W-6,35")
      (footprint "eagle-import:1704994")
      (fields (field (name "MPN") "1704994"))
      (libsource (lib "eagle-import") (part "ZFKDSA1-W-6,35"))
    )
  )
  (nets
    (net (code "1") (name "+3V3") (class "Default")
      (node (ref "C24") (pin "1") (pinfunction "1_1") (pintype "passive"))
      (node (ref "C66") (pin "1") (pinfunction "1_1") (pintype "passive"))
      (node (ref "C68") (pin "1") (pinfunction "1_1") (pintype "passive"))
      (node (ref "IC11") (pin "1") (pinfunction "OUT_1") (pintype "bidirectional"))
      (node (ref "IC12") (pin "5") (pinfunction "V+_5") (pintype "power_in"))
      (node (ref "IC13") (pin "5") (pinfunction "V+_5") (pintype "power_in"))
      (node (ref "IC4") (pin "5") (pinfunction "V+_5") (pintype "power_in"))
      (node (ref "IC5") (pin "1") (pinfunction "VCC_1") (pintype "bidirectional"))
      (node (ref "IC9") (pin "5") (pinfunction "V+_5") (pintype "power_in"))
      (node (ref "LED1") (pin "A") (pinfunction "A_A") (pintype "passive"))
      (node (ref "LED2") (pin "A") (pinfunction "A_A") (pintype "passive"))
      (node (ref "LED4") (pin "A") (pinfunction "A_A") (pintype "passive"))
      (node (ref "LED5") (pin "A") (pinfunction "A_A") (pintype "passive"))
      (node (ref "LED6") (pin "A") (pinfunction "A_A") (pintype "passive"))
      (node (ref "LED7") (pin "A") (pinfunction "A_A") (pintype "passive"))
      (node (ref "R57") (pin "2") (pinfunction "2_2") (pintype "passive"))
      (node (ref "R59") (pin "2") (pinfunction "2_2") (pintype "passive"))
      (node (ref "R63") (pin "2") (pinfunction "2_2") (pintype "passive"))
      (node (ref "R71") (pin "2") (pinfunction "2_2") (pintype "passive"))
      (node (ref "R73") (pin "2") (pinfunction "2_2") (pintype "passive"))
      (node (ref "R75") (pin "2") (pinfunction "2_2") (pintype "passive"))
    )
    (net (code "2") (name "5V_AUX_1") (class "Default")
      (node (ref "C60") (pin "1") (pinfunction "1_1") (pintype "passive"))
      (node (ref "IC1") (pin "10") (pinfunction "VOUT_10") (pintype "power_in"))
      (node (ref "IC1") (pin "9") (pinfunction "VOUT_9") (pintype "power_in"))
      (node (ref "SJ6") (pin "1") (pinfunction "1_1") (pintype "passive"))
      (node (ref "X8") (pin "1") (pinfunction "1_1") (pintype "passive"))
      (node (ref "X8") (pin "2") (pinfunction "1_2") (pintype "passive"))
    )
    (net (code "3") (name "5V_AUX_2") (class "Default")
      (node (ref "C62") (pin "1") (pinfunction "1_1") (pintype "passive"))
      (node (ref "IC6") (pin "10") (pinfunction "VOUT_10") (pintype "power_in"))
      (node (ref "IC6") (pin "9") (pinfunction "VOUT_9") (pintype "power_in"))
      (node (ref "SJ7") (pin "1") (pinfunction "1_1") (pintype "passive"))
      (node (ref "X10") (pin "1") (pinfunction "1_1") (pintype "passive"))
      (node (ref "X10") (pin "2") (pinfunction "1_2") (pintype "passive"))
    )
    (net (code "4") (name "5V_AUX_3") (class "Default")
      (node (ref "C64") (pin "1") (pinfunction "1_1") (pintype "passive"))
      (node (ref "IC10") (pin "10") (pinfunction "VOUT_10") (pintype "power_in"))
      (node (ref "IC10") (pin "9") (pinfunction "VOUT_9") (pintype "power_in"))
      (node (ref "SJ8") (pin "1") (pinfunction "1_1") (pintype "passive"))
      (node (ref "X12") (pin "1") (pinfunction "1_1") (pintype "passive"))
      (node (ref "X12") (pin "2") (pinfunction "1_2") (pintype "passive"))
    )
    (net (code "5") (name "BOOST_OUT") (class "Default")
      (node (ref "C10") (pin "1") (pinfunction "1_1") (pintype "passive"))
      (node (ref "C11") (pin "1") (pinfunction "1_1") (pintype "passive"))
      (node (ref "C12") (pin "1") (pinfunction "1_1") (pintype "passive"))
      (node (ref "C13") (pin "1") (pinfunction "1_1") (pintype "passive"))
      (node (ref "C15") (pin "2") (pinfunction "+_2") (pintype "passive"))
      (node (ref "C16") (pin "2") (pinfunction "+_2") (pintype "passive"))
      (node (ref "C57") (pin "1") (pinfunction "1_1") (pintype "passive"))
      (node (ref "C6") (pin "1") (pinfunction "1_1") (pintype "passive"))
      (node (ref "C7") (pin "1") (pinfunction "1_1") (pintype "passive"))
      (node (ref "C8") (pin "1") (pinfunction "1_1") (pintype "passive"))
      (node (ref "C9") (pin "1") (pinfunction "1_1") (pintype "passive"))
      (node (ref "Q1") (pin "5") (pinfunction "D_5") (pintype "passive"))
      (node (ref "Q1") (pin "6") (pinfunction "D_6") (pintype "passive"))
      (node (ref "Q1") (pin "7") (pinfunction "D_7") (pintype "passive"))
      (node (ref "Q1") (pin "8") (pinfunction "D_8") (pintype "passive"))
      (node (ref "Q1") (pin "TH") (pinfunction "D_TH") (pintype "passive"))
      (node (ref "Q7") (pin "5") (pinfunction "D_5") (pintype "passive"))
      (node (ref "Q7") (pin "6") (pinfunction "D_6") (pintype "passive"))
      (node (ref "Q7") (pin "7") (pinfunction "D_7") (pintype "passive"))
      (node (ref "Q7") (pin "8") (pinfunction "D_8") (pintype "passive"))
      (node (ref "Q7") (pin "TH") (pinfunction "D_TH") (pintype "passive"))
      (node (ref "SJ2") (pin "2") (pinfunction "2_2") (pintype "passive"))
      (node (ref "SJ3") (pin "2") (pinfunction "2_2") (pintype "passive"))
      (node (ref "SJ4") (pin "2") (pinfunction "2_2") (pintype "passive"))
      (node (ref "X6") (pin "1") (pinfunction "1_1") (pintype "passive"))
      (node (ref "X6") (pin "2") (pinfunction "1_2") (pintype "passive"))
    )
    (net (code "6") (name "BOOST_PG") (class "Default")
      (node (ref "IC2") (pin "25") (pinfunction "PGOOD_25") (pintype "bidirectional"))
      (node (ref "Q11") (pin "5") (pinfunction "G_5") (pintype "passive"))
      (node (ref "R57") (pin "1") (pinfunction "1_1") (pintype "passive"))
    )
    (net (code "7") (name "CURRENT_SENSE") (class "Default")
      (node (ref "IC5") (pin "3") (pinfunction "VIOUT_3") (pintype "bidirectional"))
      (node (ref "SJ5") (pin "1") (pinfunction "1_1") (pintype "passive"))
      (node (ref "X5") (pin "1") (pinfunction "1_1") (pintype "passive"))
      (node (ref "X5") (pin "2") (pinfunction "1_2") (pintype "passive"))
    )
    (net (code "8") (name "EN_VBAT1") (class "Default")
      (node (ref "IC8") (pin "6") (pinfunction "EN_6") (pintype "bidirectional"))
      (node (ref "IC8") (pin "7") (pinfunction "~{SLEEP}_7") (pintype "bidirectional"))
      (node (ref "R55") (pin "2") (pinfunction "2_2") (pintype "passive"))
      (node (ref "SW1") (pin "3") (pinfunction "3_3") (pintype "bidirectional"))
    )
    (net (code "9") (name "EN_VBAT2") (class "Default")
      (node (ref "IC3") (pin "6") (pinfunction "EN_6") (pintype "bidirectional"))
      (node (ref "IC3") (pin "7") (pinfunction "~{SLEEP}_7") (pintype "bidirectional"))
      (node (ref "R29") (pin "2") (pinfunction "2_2") (pintype "passive"))
      (node (ref "SW1") (pin "6") (pinfunction "6_6") (pintype "bidirectional"))
    )
    (net (code "10") (name "EXTVCC") (class "Default")
      (node (ref "C54") (pin "1") (pinfunction "1_1") (pintype "passive"))
      (node (ref "IC2") (pin "18") (pinfunction "EXTVCC_18") (pintype "bidirectional"))
      (node (ref "SJ1") (pin "2") (pinfunction "2_2") (pintype "passive"))
    )
    (net (code "11") (name "FLT1") (class "Default")
      (node (ref "IC8") (pin "12") (pinfunction "~{FLT}_12") (pintype "bidirectional"))
      (node (ref "TP1") (pin "TP") (pinfunction "TP_TP") (pintype "input"))
    )
    (net (code "12") (name "FLT2") (class "Default")
      (node (ref "IC3") (pin "12") (pinfunction "~{FLT}_12") (pintype "bidirectional"))
      (node (ref "TP2") (pin "TP") (pinfunction "TP_TP") (pintype "input"))
    )
    (net (code "13") (name "GND") (class "Default")
      (node (ref "C1") (pin "2") (pinfunction "2_2") (pintype "passive"))
      (node (ref "C10") (pin "2") (pinfunction "2_2") (pintype "passive"))
      (node (ref "C101") (pin "2") (pinfunction "2_2") (pintype "passive"))
      (node (ref "C102") (pin "2") (pinfunction "2_2") (pintype "passive"))
      (node (ref "C103") (pin "2") (pinfunction "2_2") (pintype "passive"))
      (node (ref "C104") (pin "2") (pinfunction "2_2") (pintype "passive"))
      (node (ref "C11") (pin "2") (pinfunction "2_2") (pintype "passive"))
      (node (ref "C12") (pin "2") (pinfunction "2_2") (pintype "passive"))
      (node (ref "C13") (pin "2") (pinfunction "2_2") (pintype "passive"))
      (node (ref "C14") (pin "1") (pinfunction "-_1") (pintype "passive"))
      (node (ref "C15") (pin "1") (pinfunction "-_1") (pintype "passive"))
      (node (ref "C16") (pin "1") (pinfunction "-_1") (pintype "passive"))
      (node (ref "C19") (pin "2") (pinfunction "2_2") (pintype "passive"))
      (node (ref "C2") (pin "2") (pinfunction "2_2") (pintype "passive"))
      (node (ref "C20") (pin "2") (pinfunction "2_2") (pintype "passive"))
      (node (ref "C22") (pin "2") (pinfunction "2_2") (pintype "passive"))
      (node (ref "C23") (pin "2") (pinfunction "2_2") (pintype "passive"))
      (node (ref "C24") (pin "2") (pinfunction "2_2") (pintype "passive"))
      (node (ref "C26") (pin "2") (pinfunction "2_2") (pintype "passive"))
      (node (ref "C27") (pin "2") (pinfunction "2_2") (pintype "passive"))
      (node (ref "C28") (pin "2") (pinfunction "2_2") (pintype "passive"))
      (node (ref "C3") (pin "2") (pinfunction "2_2") (pintype "passive"))
      (node (ref "C30") (pin "2") (pinfunction "2_2") (pintype "passive"))
      (node (ref "C31") (pin "2") (pinfunction "2_2") (pintype "passive"))
      (node (ref "C32") (pin "2") (pinfunction "2_2") (pintype "passive"))
      (node (ref "C33") (pin "2") (pinfunction "2_2") (pintype "passive"))
      (node (ref "C34") (pin "2") (pinfunction "2_2") (pintype "passive"))
      (node (ref "C35") (pin "2") (pinfunction "2_2") (pintype "passive"))
      (node (ref "C37") (pin "2") (pinfunction "2_2") (pintype "passive"))
      (node (ref "C4") (pin "2") (pinfunction "2_2") (pintype "passive"))
      (node (ref "C40") (pin "1") (pinfunction "1_1") (pintype "passive"))
      (node (ref "C41") (pin "2") (pinfunction "2_2") (pintype "passive"))
      (node (ref "C42") (pin "2") (pinfunction "2_2") (pintype "passive"))
      (node (ref "C45") (pin "1") (pinfunction "1_1") (pintype "passive"))
      (node (ref "C46") (pin "2") (pinfunction "2_2") (pintype "passive"))
      (node (ref "C47") (pin "2") (pinfunction "2_2") (pintype "passive"))
      (node (ref "C5") (pin "2") (pinfunction "2_2") (pintype "passive"))
      (node (ref "C53") (pin "2") (pinfunction "2_2") (pintype "passive"))
      (node (ref "C54") (pin "2") (pinfunction "2_2") (pintype "passive"))
      (node (ref "C55") (pin "2") (pinfunction "2_2") (pintype "passive"))
      (node (ref "C56") (pin "2") (pinfunction "2_2") (pintype "passive"))
      (node (ref "C6") (pin "2") (pinfunction "2_2") (pintype "passive"))
      (node (ref "C60") (pin "2") (pinfunction "2_2") (pintype "passive"))
      (node (ref "C61") (pin "2") (pinfunction "2_2") (pintype "passive"))
      (node (ref "C62") (pin "2") (pinfunction "2_2") (pintype "passive"))
      (node (ref "C63") (pin "2") (pinfunction "2_2") (pintype "passive"))
      (node (ref "C64") (pin "2") (pinfunction "2_2") (pintype "passive"))
      (node (ref "C65") (pin "2") (pinfunction "2_2") (pintype "passive"))
      (node (ref "C66") (pin "2") (pinfunction "2_2") (pintype "passive"))
      (node (ref "C67") (pin "2") (pinfunction "2_2") (pintype "passive"))
      (node (ref "C68") (pin "2") (pinfunction "2_2") (pintype "passive"))
      (node (ref "C7") (pin "2") (pinfunction "2_2") (pintype "passive"))
      (node (ref "C79") (pin "2") (pinfunction "2_2") (pintype "passive"))
      (node (ref "C8") (pin "2") (pinfunction "2_2") (pintype "passive"))
      (node (ref "C80") (pin "2") (pinfunction "2_2") (pintype "passive"))
      (node (ref "C81") (pin "2") (pinfunction "2_2") (pintype "passive"))
      (node (ref "C83") (pin "2") (pinfunction "2_2") (pintype "passive"))
      (node (ref "C84") (pin "2") (pinfunction "2_2") (pintype "passive"))
      (node (ref "C85") (pin "2") (pinfunction "2_2") (pintype "passive"))
      (node (ref "C86") (pin "2") (pinfunction "2_2") (pintype "passive"))
      (node (ref "C9") (pin "2") (pinfunction "2_2") (pintype "passive"))
      (node (ref "C97") (pin "2") (pinfunction "2_2") (pintype "passive"))
      (node (ref "C98") (pin "2") (pinfunction "2_2") (pintype "passive"))
      (node (ref "C99") (pin "2") (pinfunction "2_2") (pintype "passive"))
      (node (ref "IC1") (pin "6") (pinfunction "GND_6") (pintype "power_in"))
      (node (ref "IC1") (pin "EP") (pinfunction "PAD_EP") (pintype "power_in"))
      (node (ref "IC10") (pin "6") (pinfunction "GND_6") (pintype "power_in"))
      (node (ref "IC10") (pin "EP") (pinfunction "PAD_EP") (pintype "power_in"))
      (node (ref "IC11") (pin "3") (pinfunction "GND_3") (pintype "bidirectional"))
      (node (ref "IC11") (pin "EP") (pinfunction "GND_EP") (pintype "bidirectional"))
      (node (ref "IC12") (pin "2") (pinfunction "V-_2") (pintype "power_in"))
      (node (ref "IC13") (pin "2") (pinfunction "V-_2") (pintype "power_in"))
      (node (ref "IC14") (pin "3") (pinfunction "AGND_3") (pintype "bidirectional"))
      (node (ref "IC14") (pin "9") (pinfunction "PGND_9") (pintype "bidirectional"))
      (node (ref "IC16") (pin "3") (pinfunction "AGND_3") (pintype "bidirectional"))
      (node (ref "IC16") (pin "9") (pinfunction "PGND_9") (pintype "bidirectional"))
      (node (ref "IC2") (pin "19") (pinfunction "PGND_19") (pintype "bidirectional"))
      (node (ref "IC2") (pin "5") (pinfunction "SGND_5") (pintype "bidirectional"))
      (node (ref "IC2") (pin "PAD") (pinfunction "PAD_PAD") (pintype "bidirectional"))
      (node (ref "IC3") (pin "13") (pinfunction "GND_13") (pintype "bidirectional"))
      (node (ref "IC4") (pin "2") (pinfunction "V-_2") (pintype "power_in"))
      (node (ref "IC5") (pin "2") (pinfunction "GND_2") (pintype "bidirectional"))
      (node (ref "IC6") (pin "6") (pinfunction "GND_6") (pintype "power_in"))
      (node (ref "IC6") (pin "EP") (pinfunction "PAD_EP") (pintype "power_in"))
      (node (ref "IC7") (pin "3") (pinfunction "AGND_3") (pintype "bidirectional"))
      (node (ref "IC7") (pin "9") (pinfunction "PGND_9") (pintype "bidirectional"))
      (node (ref "IC8") (pin "13") (pinfunction "GND_13") (pintype "bidirectional"))
      (node (ref "IC9") (pin "2") (pinfunction "V-_2") (pintype "power_in"))
      (node (ref "Q10") (pin "1") (pinfunction "S_1") (pintype "passive"))
      (node (ref "Q10") (pin "4") (pinfunction "S_4") (pintype "passive"))
      (node (ref "Q11") (pin "1") (pinfunction "S_1") (pintype "passive"))
      (node (ref "Q11") (pin "4") (pinfunction "S_4") (pintype "passive"))
      (node (ref "Q6") (pin "1") (pinfunction "S_1") (pintype "passive"))
      (node (ref "Q6") (pin "2") (pinfunction "S_2") (pintype "passive"))
      (node (ref "Q6") (pin "3") (pinfunction "S_3") (pintype "passive"))
      (node (ref "Q8") (pin "1") (pinfunction "S_1") (pintype "passive"))
      (node (ref "Q8") (pin "2") (pinfunction "S_2") (pintype "passive"))
      (node (ref "Q8") (pin "3") (pinfunction "S_3") (pintype "passive"))
      (node (ref "Q9") (pin "1") (pinfunction "S_1") (pintype "passive"))
      (node (ref "Q9") (pin "4") (pinfunction "S_4") (pintype "passive"))
      (node (ref "R10") (pin "1") (pinfunction "1_1") (pintype "passive"))
      (node (ref "R101") (pin "1") (pinfunction "1_1") (pintype "passive"))
      (node (ref "R102") (pin "1") (pinfunction "1_1") (pintype "passive"))
      (node (ref "R12") (pin "1") (pinfunction "1_1") (pintype "passive"))
      (node (ref "R14") (pin "1") (pinfunction "1_1") (pintype "passive"))
      (node (ref "R18") (pin "1") (pinfunction "1_1") (pintype "passive"))
      (node (ref "R22") (pin "1") (pinfunction "1_1") (pintype "passive"))
      (node (ref "R29") (pin "1") (pinfunction "1_1") (pintype "passive"))
      (node (ref "R33") (pin "1") (pinfunction "1_1") (pintype "passive"))
      (node (ref "R37") (pin "1") (pinfunction "1_1") (pintype "passive"))
      (node (ref "R39") (pin "1") (pinfunction "1_1") (pintype "passive"))
      (node (ref "R4") (pin "1") (pinfunction "1_1") (pintype "passive"))
      (node (ref "R40") (pin "1") (pinfunction "1_1") (pintype "passive"))
      (node (ref "R48") (pin "1") (pinfunction "1_1") (pintype "passive"))
      (node (ref "R49") (pin "1") (pinfunction "1_1") (pintype "passive"))
      (node (ref "R5") (pin "1") (pinfunction "1_1") (pintype "passive"))
      (node (ref "R52") (pin "1") (pinfunction "1_1") (pintype "passive"))
      (node (ref "R55") (pin "1") (pinfunction "1_1") (pintype "passive"))
      (node (ref "R62") (pin "1") (pinfunction "1_1") (pintype "passive"))
      (node (ref "R65") (pin "1") (pinfunction "1_1") (pintype "passive"))
      (node (ref "R66") (pin "1") (pinfunction "1_1") (pintype "passive"))
      (node (ref "R67") (pin "1") (pinfunction "1_1") (pintype "passive"))
      (node (ref "R69") (pin "1") (pinfunction "1_1") (pintype "passive"))
      (node (ref "R70") (pin "1") (pinfunction "1_1") (pintype "passive"))
      (node (ref "R77") (pin "1") (pinfunction "1_1") (pintype "passive"))
      (node (ref "R8") (pin "1") (pinfunction "1_1") (pintype "passive"))
      (node (ref "R80") (pin "1") (pinfunction "1_1") (pintype "passive"))
      (node (ref "R81") (pin "1") (pinfunction "1_1") (pintype "passive"))
      (node (ref "R82") (pin "1") (pinfunction "1_1") (pintype "passive"))
      (node (ref "R83") (pin "1") (pinfunction "1_1") (pintype "passive"))
      (node (ref "R84") (pin "1") (pinfunction "1_1") (pintype "passive"))
      (node (ref "R87") (pin "1") (pinfunction "1_1") (pintype "passive"))
      (node (ref "R89") (pin "1") (pinfunction "1_1") (pintype "passive"))
      (node (ref "R90") (pin "1") (pinfunction "1_1") (pintype "passive"))
      (node (ref "R99") (pin "1") (pinfunction "1_1") (pintype "passive"))
      (node (ref "TP3") (pin "TP") (pinfunction "TP_TP") (pintype "input"))
      (node (ref "TP4") (pin "TP") (pinfunction "TP_TP") (pintype "input"))
      (node (ref "X1") (pin "NEG") (pinfunction "2_NEG") (pintype "passive"))
      (node (ref "X11") (pin "1") (pinfunction "1_1") (pintype "passive"))
      (node (ref "X11") (pin "2") (pinfunction "1_2") (pintype "passive"))
      (node (ref "X13") (pin "1") (pinfunction "1_1") (pintype "passive"))
      (node (ref "X13") (pin "2") (pinfunction "1_2") (pintype "passive"))
      (node (ref "X15") (pin "1") (pinfunction "1_1") (pintype "passive"))
      (node (ref "X15") (pin "2") (pinfunction "1_2") (pintype "passive"))
      (node (ref "X17") (pin "1") (pinfunction "1_1") (pintype "passive"))
      (node (ref "X17") (pin "2") (pinfunction "1_2") (pintype "passive"))
      (node (ref "X2") (pin "NEG") (pinfunction "2_NEG") (pintype "passive"))
      (node (ref "X3") (pin "NEG") (pinfunction "2_NEG") (pintype "passive"))
      (node (ref "X7") (pin "1") (pinfunction "1_1") (pintype "passive"))
      (node (ref "X7") (pin "2") (pinfunction "1_2") (pintype "passive"))
      (node (ref "X9") (pin "1") (pinfunction "1_1") (pintype "passive"))
      (node (ref "X9") (pin "2") (pinfunction "1_2") (pintype "passive"))
    )
    (net (code "14") (name "IMON1") (class "Default")
      (node (ref "IC8") (pin "10") (pinfunction "IMON_10") (pintype "bidirectional"))
      (node (ref "IC9") (pin "1") (pinfunction "+IN_1") (pintype "input"))
      (node (ref "R49") (pin "2") (pinfunction "2_2") (pintype "passive"))
    )
    (net (code "15") (name "IMON2") (class "Default")
      (node (ref "IC13") (pin "1") (pinfunction "+IN_1") (pintype "input"))
      (node (ref "IC3") (pin "10") (pinfunction "IMON_10") (pintype "bidirectional"))
      (node (ref "R81") (pin "2") (pinfunction "2_2") (pintype "passive"))
    )
    (net (code "16") (name "INTVCC") (class "Default")
      (node (ref "C20") (pin "1") (pinfunction "1_1") (pintype "passive"))
      (node (ref "D1") (pin "A") (pinfunction "A_A") (pintype "passive"))
      (node (ref "D2") (pin "A") (pinfunction "A_A") (pintype "passive"))
      (node (ref "IC2") (pin "17") (pinfunction "INTVCC_17") (pintype "bidirectional"))
      (node (ref "R11") (pin "2") (pinfunction "2_2") (pintype "passive"))
      (node (ref "R13") (pin "2") (pinfunction "2_2") (pintype "passive"))
      (node (ref "R16") (pin "2") (pinfunction "2_2") (pintype "passive"))
      (node (ref "R9") (pin "2") (pinfunction "2_2") (pintype "passive"))
    )
    (net (code "17") (name "Net-(C29-Pad1)") (class "Default")
      (node (ref "C29") (pin "1") (pinfunction "1_1") (pintype "passive"))
      (node (ref "R41") (pin "2") (pinfunction "2_2") (pintype "passive"))
      (node (ref "R42") (pin "1") (pinfunction "1_1") (pintype "passive"))
    )
    (net (code "18") (name "Net-(C40-Pad2)") (class "Default")
      (node (ref "C40") (pin "2") (pinfunction "2_2") (pintype "passive"))
      (node (ref "R46") (pin "1") (pinfunction "1_1") (pintype "passive"))
    )
    (net (code "19") (name "Net-(C45-Pad2)") (class "Default")
      (node (ref "C45") (pin "2") (pinfunction "2_2") (pintype "passive"))
      (node (ref "R19") (pin "1") (pinfunction "1_1") (pintype "passive"))
    )
    (net (code "20") (name "Net-(C55-Pad1)") (class "Default")
      (node (ref "C55") (pin "1") (pinfunction "1_1") (pintype "passive"))
      (node (ref "R23") (pin "1") (pinfunction "1_1") (pintype "passive"))
    )
    (net (code "21") (name "Net-(C82-Pad1)") (class "Default")
      (node (ref "C82") (pin "1") (pinfunction "1_1") (pintype "passive"))
      (node (ref "R91") (pin "2") (pinfunction "2_2") (pintype "passive"))
      (node (ref "R92") (pin "1") (pinfunction "1_1") (pintype "passive"))
    )
    (net (code "22") (name "Net-(C100-Pad1)") (class "Default")
      (node (ref "C100") (pin "1") (pinfunction "1_1") (pintype "passive"))
      (node (ref "R104") (pin "1") (pinfunction "1_1") (pintype "passive"))
      (node (ref "R43") (pin "2") (pinfunction "2_2") (pintype "passive"))
    )
    (net (code "23") (name "Net-(IC1-EN)") (class "Default")
      (node (ref "IC1") (pin "4") (pinfunction "EN_4") (pintype "input"))
      (node (ref "R3") (pin "1") (pinfunction "1_1") (pintype "passive"))
      (node (ref "R4") (pin "2") (pinfunction "2_2") (pintype "passive"))
    )
    (net (code "24") (name "Net-(IC1-ILIM{slash}IMON)") (class "Default")
      (node (ref "IC1") (pin "5") (pinfunction "ILIM/IMON_5") (pintype "output"))
      (node (ref "R65") (pin "2") (pinfunction "2_2") (pintype "passive"))
    )
    (net (code "25") (name "Net-(IC1-SS)") (class "Default")
      (node (ref "C47") (pin "1") (pinfunction "1_1") (pintype "passive"))
      (node (ref "IC1") (pin "3") (pinfunction "SS_3") (pintype "passive"))
    )
    (net (code "26") (name "Net-(IC2-BG1)") (class "Default")
      (node (ref "IC2") (pin "21") (pinfunction "BG1_21") (pintype "bidirectional"))
      (node (ref "Q6") (pin "4") (pinfunction "G_4") (pintype "passive"))
    )
    (net (code "27") (name "Net-(IC2-BG2)") (class "Default")
      (node (ref "IC2") (pin "16") (pinfunction "BG2_16") (pintype "bidirectional"))
      (node (ref "Q8") (pin "4") (pinfunction "G_4") (pintype "passive"))
    )
    (net (code "28") (name "Net-(IC2-BOOST1)") (class "Default")
      (node (ref "C18") (pin "1") (pinfunction "1_1") (pintype "passive"))
      (node (ref "D2") (pin "C") (pinfunction "C_C") (pintype "passive"))
      (node (ref "IC2") (pin "22") (pinfunction "BOOST1_22") (pintype "bidirectional"))
    )
    (net (code "29") (name "Net-(IC2-BOOST2)") (class "Default")
      (node (ref "C17") (pin "2") (pinfunction "2_2") (pintype "passive"))
      (node (ref "D1") (pin "C") (pinfunction "C_C") (pintype "passive"))
      (node (ref "IC2") (pin "15") (pinfunction "BOOST2_15") (pintype "bidirectional"))
    )
    (net (code "30") (name "Net-(IC2-FREQ)") (class "Default")
      (node (ref "IC2") (pin "1") (pinfunction "FREQ_1") (pintype "bidirectional"))
      (node (ref "R8") (pin "2") (pinfunction "2_2") (pintype "passive"))
      (node (ref "R9") (pin "1") (pinfunction "1_1") (pintype "passive"))
    )
    (net (code "31") (name "Net-(IC2-ILIM)") (class "Default")
      (node (ref "IC2") (pin "26") (pinfunction "ILIM_26") (pintype "bidirectional"))
      (node (ref "R16") (pin "1") (pinfunction "1_1") (pintype "passive"))
      (node (ref "R18") (pin "2") (pinfunction "2_2") (pintype "passive"))
    )
    (net (code "32") (name "Net-(IC2-ITH)") (class "Default")
      (node (ref "C56") (pin "1") (pinfunction "1_1") (pintype "passive"))
      (node (ref "IC2") (pin "11") (pinfunction "ITH_11") (pintype "bidirectional"))
      (node (ref "R23") (pin "2") (pinfunction "2_2") (pintype "passive"))
    )
    (net (code "33") (name "Net-(IC2-PHASMD)") (class "Default")
      (node (ref "IC2") (pin "2") (pinfunction "PHASMD_2") (pintype "bidirectional"))
      (node (ref "R10") (pin "2") (pinfunction "2_2") (pintype "passive"))
      (node (ref "R11") (pin "1") (pinfunction "1_1") (pintype "passive"))
    )
    (net (code "34") (name "Net-(IC2-PLLIN{slash}MODE)") (class "Default")
      (node (ref "IC2") (pin "4") (pinfunction "PLLIN/MODE_4") (pintype "bidirectional"))
      (node (ref "R12") (pin "2") (pinfunction "2_2") (pintype "passive"))
      (node (ref "R13") (pin "1") (pinfunction "1_1") (pintype "passive"))
    )
    (net (code "35") (name "Net-(IC2-RUN)") (class "Default")
      (node (ref "IC2") (pin "6") (pinfunction "RUN_6") (pintype "bidirectional"))
      (node (ref "R14") (pin "2") (pinfunction "2_2") (pintype "passive"))
      (node (ref "R15") (pin "1") (pinfunction "1_1") (pintype "passive"))
    )
    (net (code "36") (name "Net-(IC2-SENSE1+)") (class "Default")
      (node (ref "C58") (pin "2") (pinfunction "2_2") (pintype "passive"))
      (node (ref "IC2") (pin "27") (pinfunction "SENSE1+_27") (pintype "bidirectional"))
      (node (ref "R27") (pin "1") (pinfunction "1_1") (pintype "passive"))
    )
    (net (code "37") (name "Net-(IC2-SENSE1-)") (class "Default")
      (node (ref "C58") (pin "1") (pinfunction "1_1") (pintype "passive"))
      (node (ref "IC2") (pin "28") (pinfunction "SENSE1-_28") (pintype "bidirectional"))
      (node (ref "R28") (pin "1") (pinfunction "1_1") (pintype "passive"))
    )
    (net (code "38") (name "Net-(IC2-SENSE2+)") (class "Default")
      (node (ref "C59") (pin "2") (pinfunction "2_2") (pintype "passive"))
      (node (ref "IC2") (pin "9") (pinfunction "SENSE2+_9") (pintype "bidirectional"))
      (node (ref "R56") (pin "2") (pinfunction "2_2") (pintype "passive"))
    )
    (net (code "39") (name "Net-(IC2-SENSE2-)") (class "Default")
      (node (ref "C59") (pin "1") (pinfunction "1_1") (pintype "passive"))
      (node (ref "IC2") (pin "8") (pinfunction "SENSE2-_8") (pintype "bidirectional"))
      (node (ref "R53") (pin "2") (pinfunction "2_2") (pintype "passive"))
    )
    (net (code "40") (name "Net-(IC2-SS)") (class "Default")
      (node (ref "C30") (pin "1") (pinfunction "1_1") (pintype "passive"))
      (node (ref "IC2") (pin "7") (pinfunction "SS_7") (pintype "bidirectional"))
    )
    (net (code "41") (name "Net-(IC2-SW1)") (class "Default")
      (node (ref "C18") (pin "2") (pinfunction "2_2") (pintype "passive"))
      (node (ref "IC2") (pin "24") (pinfunction "SW1_24") (pintype "bidirectional"))
      (node (ref "L1") (pin "1") (pinfunction "1_1") (pintype "passive"))
      (node (ref "Q1") (pin "1") (pinfunction "S_1") (pintype "passive"))
      (node (ref "Q1") (pin "2") (pinfunction "S_2") (pintype "passive"))
      (node (ref "Q1") (pin "3") (pinfunction "S_3") (pintype "passive"))
      (node (ref "Q6") (pin "5") (pinfunction "D_5") (pintype "passive"))
      (node (ref "Q6") (pin "6") (pinfunction "D_6") (pintype "passive"))
      (node (ref "Q6") (pin "7") (pinfunction "D_7") (pintype "passive"))
      (node (ref "Q6") (pin "8") (pinfunction "D_8") (pintype "passive"))
      (node (ref "Q6") (pin "TH") (pinfunction "D_TH") (pintype "passive"))
    )
    (net (code "42") (name "Net-(IC2-SW2)") (class "Default")
      (node (ref "C17") (pin "1") (pinfunction "1_1") (pintype "passive"))
      (node (ref "IC2") (pin "13") (pinfunction "SW2_13") (pintype "bidirectional"))
      (node (ref "L2") (pin "1") (pinfunction "1_1") (pintype "passive"))
      (node (ref "Q7") (pin "1") (pinfunction "S_1") (pintype "passive"))
      (node (ref "Q7") (pin "2") (pinfunction "S_2") (pintype "passive"))
      (node (ref "Q7") (pin "3") (pinfunction "S_3") (pintype "passive"))
      (node (ref "Q8") (pin "5") (pinfunction "D_5") (pintype "passive"))
      (node (ref "Q8") (pin "6") (pinfunction "D_6") (pintype "passive"))
      (node (ref "Q8") (pin "7") (pinfunction "D_7") (pintype "passive"))
      (node (ref "Q8") (pin "8") (pinfunction "D_8") (pintype "passive"))
      (node (ref "Q8") (pin "TH") (pinfunction "D_TH") (pintype "passive"))
    )
    (net (code "43") (name "Net-(IC2-TG1)") (class "Default")
      (node (ref "IC2") (pin "23") (pinfunction "TG1_23") (pintype "bidirectional"))
      (node (ref "Q1") (pin "4") (pinfunction "G_4") (pintype "passive"))
    )
    (net (code "44") (name "Net-(IC2-TG2)") (class "Default")
      (node (ref "IC2") (pin "14") (pinfunction "TG2_14") (pintype "bidirectional"))
      (node (ref "Q7") (pin "4") (pinfunction "G_4") (pintype "passive"))
    )
    (net (code "45") (name "Net-(IC2-VFB)") (class "Default")
      (node (ref "C57") (pin "2") (pinfunction "2_2") (pintype "passive"))
      (node (ref "IC2") (pin "10") (pinfunction "VFB_10") (pintype "bidirectional"))
      (node (ref "R22") (pin "2") (pinfunction "2_2") (pintype "passive"))
      (node (ref "R24") (pin "2") (pinfunction "2_2") (pintype "passive"))
      (node (ref "R25") (pin "1") (pinfunction "1_1") (pintype "passive"))
      (node (ref "R26") (pin "1") (pinfunction "1_1") (pintype "passive"))
    )
    (net (code "46") (name "Net-(IC3-C)") (class "Default")
      (node (ref "C21") (pin "1") (pinfunction "1_1") (pintype "passive"))
      (node (ref "C41") (pin "1") (pinfunction "1_1") (pintype "passive"))
      (node (ref "IC3") (pin "22") (pinfunction "VS_22") (pintype "bidirectional"))
      (node (ref "IC3") (pin "24") (pinfunction "C_24") (pintype "bidirectional"))
      (node (ref "Q4") (pin "5") (pinfunction "D_5") (pintype "passive"))
      (node (ref "Q4") (pin "6") (pinfunction "D_6") (pintype "passive"))
      (node (ref "Q4") (pin "7") (pinfunction "D_7") (pintype "passive"))
      (node (ref "Q4") (pin "8") (pinfunction "D_8") (pintype "passive"))
      (node (ref "Q4") (pin "TH") (pinfunction "D_TH") (pintype "passive"))
      (node (ref "R30") (pin "1A") (pinfunction "1A_1A") (pintype "passive"))
      (node (ref "R51") (pin "2") (pinfunction "2_2") (pintype "passive"))
    )
    (net (code "47") (name "Net-(IC3-CAP)") (class "Default")
      (node (ref "C21") (pin "2") (pinfunction "2_2") (pintype "passive"))
      (node (ref "IC3") (pin "23") (pinfunction "CAP_23") (pintype "bidirectional"))
    )
    (net (code "48") (name "Net-(IC3-CS+)") (class "Default")
      (node (ref "C43") (pin "1") (pinfunction "1_1") (pintype "passive"))
      (node (ref "IC3") (pin "20") (pinfunction "CS+_20") (pintype "bidirectional"))
      (node (ref "R50") (pin "1") (pinfunction "1_1") (pintype "passive"))
    )
    (net (code "49") (name "Net-(IC3-CS-)") (class "Default")
      (node (ref "C43") (pin "2") (pinfunction "2_2") (pintype "passive"))
      (node (ref "C44") (pin "2") (pinfunction "2_2") (pintype "passive"))
      (node (ref "IC3") (pin "19") (pinfunction "CS-_19") (pintype "bidirectional"))
      (node (ref "R30") (pin "2B") (pinfunction "2B_2B") (pintype "passive"))
    )
    (net (code "50") (name "Net-(IC3-DGATE)") (class "Default")
      (node (ref "IC3") (pin "1") (pinfunction "DGATE_1") (pintype "bidirectional"))
      (node (ref "Q4") (pin "4") (pinfunction "G_4") (pintype "passive"))
    )
    (net (code "51") (name "Net-(IC3-HGATE)") (class "Default")
      (node (ref "IC3") (pin "14") (pinfunction "HGATE_14") (pintype "bidirectional"))
      (node (ref "Q5") (pin "4") (pinfunction "G_4") (pintype "passive"))
      (node (ref "R19") (pin "2") (pinfunction "2_2") (pintype "passive"))
    )
    (net (code "52") (name "Net-(IC3-ILIM)") (class "Default")
      (node (ref "IC3") (pin "11") (pinfunction "ILIM_11") (pintype "bidirectional"))
      (node (ref "R84") (pin "2") (pinfunction "2_2") (pintype "passive"))
    )
    (net (code "53") (name "Net-(IC3-ISCP)") (class "Default")
      (node (ref "C44") (pin "1") (pinfunction "1_1") (pintype "passive"))
      (node (ref "IC3") (pin "18") (pinfunction "ISCP_18") (pintype "bidirectional"))
      (node (ref "R51") (pin "1") (pinfunction "1_1") (pintype "passive"))
    )
    (net (code "54") (name "Net-(IC3-OV)") (class "Default")
      (node (ref "IC3") (pin "5") (pinfunction "OV_5") (pintype "bidirectional"))
      (node (ref "R21") (pin "1") (pinfunction "1_1") (pintype "passive"))
      (node (ref "R83") (pin "2") (pinfunction "2_2") (pintype "passive"))
    )
    (net (code "55") (name "Net-(IC3-SW)") (class "Default")
      (node (ref "IC3") (pin "3") (pinfunction "SW_3") (pintype "bidirectional"))
      (node (ref "R20") (pin "2") (pinfunction "2_2") (pintype "passive"))
      (node (ref "R21") (pin "2") (pinfunction "2_2") (pintype "passive"))
    )
    (net (code "56") (name "Net-(IC3-TMR)") (class "Default")
      (node (ref "C46") (pin "1") (pinfunction "1_1") (pintype "passive"))
      (node (ref "IC3") (pin "9") (pinfunction "TMR_9") (pintype "bidirectional"))
    )
    (net (code "57") (name "Net-(IC3-UVLO)") (class "Default")
      (node (ref "IC3") (pin "4") (pinfunction "UVLO_4") (pintype "bidirectional"))
      (node (ref "R20") (pin "1") (pinfunction "1_1") (pintype "passive"))
      (node (ref "R82") (pin "2") (pinfunction "2_2") (pintype "passive"))
    )
    (net (code "58") (name "Net-(IC4-+IN)") (class "Default")
      (node (ref "IC4") (pin "1") (pinfunction "+IN_1") (pintype "input"))
      (node (ref "R17") (pin "2") (pinfunction "2_2") (pintype "passive"))
      (node (ref "R31") (pin "2") (pinfunction "2_2") (pintype "passive"))
    )
    (net (code "59") (name "Net-(IC4--IN)") (class "Default")
      (node (ref "IC4") (pin "3") (pinfunction "-IN_3") (pintype "input"))
      (node (ref "R32") (pin "1") (pinfunction "1_1") (pintype "passive"))
      (node (ref "R33") (pin "2") (pinfunction "2_2") (pintype "passive"))
    )
    (net (code "60") (name "Net-(IC4-OUT)") (class "Default")
      (node (ref "IC4") (pin "4") (pinfunction "OUT_4") (pintype "output"))
      (node (ref "R32") (pin "2") (pinfunction "2_2") (pintype "passive"))
      (node (ref "SJ5") (pin "2") (pinfunction "2_2") (pintype "passive"))
    )
    (net (code "61") (name "Net-(IC6-EN)") (class "Default")
      (node (ref "IC6") (pin "4") (pinfunction "EN_4") (pintype "input"))
      (node (ref "R1") (pin "1") (pinfunction "1_1") (pintype "passive"))
      (node (ref "R66") (pin "2") (pinfunction "2_2") (pintype "passive"))
    )
    (net (code "62") (name "Net-(IC6-ILIM{slash}IMON)") (class "Default")
      (node (ref "IC6") (pin "5") (pinfunction "ILIM/IMON_5") (pintype "output"))
      (node (ref "R67") (pin "2") (pinfunction "2_2") (pintype "passive"))
    )
    (net (code "63") (name "Net-(IC6-SS)") (class "Default")
      (node (ref "C23") (pin "1") (pinfunction "1_1") (pintype "passive"))
      (node (ref "IC6") (pin "3") (pinfunction "SS_3") (pintype "passive"))
    )
    (net (code "64") (name "Net-(IC7-BOOT)") (class "Default")
      (node (ref "C25") (pin "2") (pinfunction "2_2") (pintype "passive"))
      (node (ref "IC7") (pin "7") (pinfunction "BOOT_7") (pintype "bidirectional"))
    )
    (net (code "65") (name "Net-(IC7-EN)") (class "Default")
      (node (ref "IC7") (pin "1") (pinfunction "EN_1") (pintype "bidirectional"))
      (node (ref "R37") (pin "2") (pinfunction "2_2") (pintype "passive"))
      (node (ref "R38") (pin "1") (pinfunction "1_1") (pintype "passive"))
    )
    (net (code "66") (name "Net-(IC7-FB)") (class "Default")
      (node (ref "C29") (pin "2") (pinfunction "2_2") (pintype "passive"))
      (node (ref "IC7") (pin "2") (pinfunction "FB_2") (pintype "bidirectional"))
      (node (ref "R40") (pin "2") (pinfunction "2_2") (pintype "passive"))
      (node (ref "R41") (pin "1") (pinfunction "1_1") (pintype "passive"))
    )
    (net (code "67") (name "Net-(IC7-MODE)") (class "Default")
      (node (ref "IC7") (pin "10") (pinfunction "MODE_10") (pintype "bidirectional"))
      (node (ref "R39") (pin "2") (pinfunction "2_2") (pintype "passive"))
    )
    (net (code "68") (name "Net-(IC7-SS)") (class "Default")
      (node (ref "C34") (pin "1") (pinfunction "1_1") (pintype "passive"))
      (node (ref "IC7") (pin "5") (pinfunction "SS_5") (pintype "bidirectional"))
    )
    (net (code "69") (name "Net-(IC7-SW)") (class "Default")
      (node (ref "C25") (pin "1") (pinfunction "1_1") (pintype "passive"))
      (node (ref "IC7") (pin "6") (pinfunction "SW_6") (pintype "bidirectional"))
      (node (ref "L3") (pin "1") (pinfunction "1_1") (pintype "passive"))
    )
    (net (code "70") (name "Net-(IC8-C)") (class "Default")
      (node (ref "C36") (pin "1") (pinfunction "1_1") (pintype "passive"))
      (node (ref "C37") (pin "1") (pinfunction "1_1") (pintype "passive"))
      (node (ref "IC8") (pin "22") (pinfunction "VS_22") (pintype "bidirectional"))
      (node (ref "IC8") (pin "24") (pinfunction "C_24") (pintype "bidirectional"))
      (node (ref "Q2") (pin "5") (pinfunction "D_5") (pintype "passive"))
      (node (ref "Q2") (pin "6") (pinfunction "D_6") (pintype "passive"))
      (node (ref "Q2") (pin "7") (pinfunction "D_7") (pintype "passive"))
      (node (ref "Q2") (pin "8") (pinfunction "D_8") (pintype "passive"))
      (node (ref "Q2") (pin "TH") (pinfunction "D_TH") (pintype "passive"))
      (node (ref "R2") (pin "1A") (pinfunction "1A_1A") (pintype "passive"))
      (node (ref "R44") (pin "2") (pinfunction "2_2") (pintype "passive"))
    )
    (net (code "71") (name "Net-(IC8-CAP)") (class "Default")
      (node (ref "C36") (pin "2") (pinfunction "2_2") (pintype "passive"))
      (node (ref "IC8") (pin "23") (pinfunction "CAP_23") (pintype "bidirectional"))
    )
    (net (code "72") (name "Net-(IC8-CS+)") (class "Default")
      (node (ref "C38") (pin "1") (pinfunction "1_1") (pintype "passive"))
      (node (ref "IC8") (pin "20") (pinfunction "CS+_20") (pintype "bidirectional"))
      (node (ref "R45") (pin "1") (pinfunction "1_1") (pintype "passive"))
    )
    (net (code "73") (name "Net-(IC8-CS-)") (class "Default")
      (node (ref "C38") (pin "2") (pinfunction "2_2") (pintype "passive"))
      (node (ref "C39") (pin "2") (pinfunction "2_2") (pintype "passive"))
      (node (ref "IC8") (pin "19") (pinfunction "CS-_19") (pintype "bidirectional"))
      (node (ref "R2") (pin "2B") (pinfunction "2B_2B") (pintype "passive"))
    )
    (net (code "74") (name "Net-(IC8-DGATE)") (class "Default")
      (node (ref "IC8") (pin "1") (pinfunction "DGATE_1") (pintype "bidirectional"))
      (node (ref "Q2") (pin "4") (pinfunction "G_4") (pintype "passive"))
    )
    (net (code "75") (name "Net-(IC8-HGATE)") (class "Default")
      (node (ref "IC8") (pin "14") (pinfunction "HGATE_14") (pintype "bidirectional"))
      (node (ref "Q3") (pin "4") (pinfunction "G_4") (pintype "passive"))
      (node (ref "R46") (pin "2") (pinfunction "2_2") (pintype "passive"))
    )
    (net (code "76") (name "Net-(IC8-ILIM)") (class "Default")
      (node (ref "IC8") (pin "11") (pinfunction "ILIM_11") (pintype "bidirectional"))
      (node (ref "R5") (pin "2") (pinfunction "2_2") (pintype "passive"))
    )
    (net (code "77") (name "Net-(IC8-ISCP)") (class "Default")
      (node (ref "C39") (pin "1") (pinfunction "1_1") (pintype "passive"))
      (node (ref "IC8") (pin "18") (pinfunction "ISCP_18") (pintype "bidirectional"))
      (node (ref "R44") (pin "1") (pinfunction "1_1") (pintype "passive"))
    )
    (net (code "78") (name "Net-(IC8-OV)") (class "Default")
      (node (ref "IC8") (pin "5") (pinfunction "OV_5") (pintype "bidirectional"))
      (node (ref "R47") (pin "1") (pinfunction "1_1") (pintype "passive"))
      (node (ref "R48") (pin "2") (pinfunction "2_2") (pintype "passive"))
    )
    (net (code "79") (name "Net-(IC8-SW)") (class "Default")
      (node (ref "IC8") (pin "3") (pinfunction "SW_3") (pintype "bidirectional"))
      (node (ref "R47") (pin "2") (pinfunction "2_2") (pintype "passive"))
      (node (ref "R54") (pin "2") (pinfunction "2_2") (pintype "passive"))
    )
    (net (code "80") (name "Net-(IC8-TMR)") (class "Default")
      (node (ref "C42") (pin "1") (pinfunction "1_1") (pintype "passive"))
      (node (ref "IC8") (pin "9") (pinfunction "TMR_9") (pintype "bidirectional"))
    )
    (net (code "81") (name "Net-(IC8-UVLO)") (class "Default")
      (node (ref "IC8") (pin "4") (pinfunction "UVLO_4") (pintype "bidirectional"))
      (node (ref "R52") (pin "2") (pinfunction "2_2") (pintype "passive"))
      (node (ref "R54") (pin "1") (pinfunction "1_1") (pintype "passive"))
    )
    (net (code "82") (name "Net-(IC9--IN)") (class "Default")
      (node (ref "IC9") (pin "3") (pinfunction "-IN_3") (pintype "input"))
      (node (ref "IC9") (pin "4") (pinfunction "OUT_4") (pintype "output"))
      (node (ref "R17") (pin "1") (pinfunction "1_1") (pintype "passive"))
    )
    (net (code "83") (name "Net-(IC10-EN)") (class "Default")
      (node (ref "IC10") (pin "4") (pinfunction "EN_4") (pintype "input"))
      (node (ref "R68") (pin "1") (pinfunction "1_1") (pintype "passive"))
      (node (ref "R69") (pin "2") (pinfunction "2_2") (pintype "passive"))
    )
    (net (code "84") (name "Net-(IC10-ILIM{slash}IMON)") (class "Default")
      (node (ref "IC10") (pin "5") (pinfunction "ILIM/IMON_5") (pintype "output"))
      (node (ref "R70") (pin "2") (pinfunction "2_2") (pintype "passive"))
    )
    (net (code "85") (name "Net-(IC10-SS)") (class "Default")
      (node (ref "C22") (pin "1") (pinfunction "1_1") (pintype "passive"))
      (node (ref "IC10") (pin "3") (pinfunction "SS_3") (pintype "passive"))
    )
    (net (code "86") (name "Net-(IC11-EN)") (class "Default")
      (node (ref "IC11") (pin "4") (pinfunction "EN_4") (pintype "bidirectional"))
      (node (ref "R77") (pin "2") (pinfunction "2_2") (pintype "passive"))
      (node (ref "R78") (pin "1") (pinfunction "1_1") (pintype "passive"))
    )
    (net (code "87") (name "Net-(IC12--IN)") (class "Default")
      (node (ref "IC12") (pin "3") (pinfunction "-IN_3") (pintype "input"))
      (node (ref "IC12") (pin "4") (pinfunction "OUT_4") (pintype "output"))
      (node (ref "R79") (pin "1") (pinfunction "1_1") (pintype "passive"))
    )
    (net (code "88") (name "Net-(IC13--IN)") (class "Default")
      (node (ref "IC13") (pin "3") (pinfunction "-IN_3") (pintype "input"))
      (node (ref "IC13") (pin "4") (pinfunction "OUT_4") (pintype "output"))
      (node (ref "R31") (pin "1") (pinfunction "1_1") (pintype "passive"))
    )
    (net (code "89") (name "Net-(IC14-BOOT)") (class "Default")
      (node (ref "C78") (pin "2") (pinfunction "2_2") (pintype "passive"))
      (node (ref "IC14") (pin "7") (pinfunction "BOOT_7") (pintype "bidirectional"))
    )
    (net (code "90") (name "Net-(IC14-EN)") (class "Default")
      (node (ref "IC14") (pin "1") (pinfunction "EN_1") (pintype "bidirectional"))
      (node (ref "R87") (pin "2") (pinfunction "2_2") (pintype "passive"))
      (node (ref "R88") (pin "1") (pinfunction "1_1") (pintype "passive"))
    )
    (net (code "91") (name "Net-(IC14-FB)") (class "Default")
      (node (ref "C82") (pin "2") (pinfunction "2_2") (pintype "passive"))
      (node (ref "IC14") (pin "2") (pinfunction "FB_2") (pintype "bidirectional"))
      (node (ref "R90") (pin "2") (pinfunction "2_2") (pintype "passive"))
      (node (ref "R91") (pin "1") (pinfunction "1_1") (pintype "passive"))
    )
    (net (code "92") (name "Net-(IC14-MODE)") (class "Default")
      (node (ref "IC14") (pin "10") (pinfunction "MODE_10") (pintype "bidirectional"))
      (node (ref "R89") (pin "2") (pinfunction "2_2") (pintype "passive"))
    )
    (net (code "93") (name "Net-(IC14-SS)") (class "Default")
      (node (ref "C86") (pin "1") (pinfunction "1_1") (pintype "passive"))
      (node (ref "IC14") (pin "5") (pinfunction "SS_5") (pintype "bidirectional"))
    )
    (net (code "94") (name "Net-(IC14-SW)") (class "Default")
      (node (ref "C78") (pin "1") (pinfunction "1_1") (pintype "passive"))
      (node (ref "IC14") (pin "6") (pinfunction "SW_6") (pintype "bidirectional"))
      (node (ref "L7") (pin "1") (pinfunction "1_1") (pintype "passive"))
    )
    (net (code "95") (name "Net-(IC16-BOOT)") (class "Default")
      (node (ref "C96") (pin "2") (pinfunction "2_2") (pintype "passive"))
      (node (ref "IC16") (pin "7") (pinfunction "BOOT_7") (pintype "bidirectional"))
    )
    (net (code "96") (name "Net-(IC16-EN)") (class "Default")
      (node (ref "IC16") (pin "1") (pinfunction "EN_1") (pintype "bidirectional"))
      (node (ref "R100") (pin "1") (pinfunction "1_1") (pintype "passive"))
      (node (ref "R99") (pin "2") (pinfunction "2_2") (pintype "passive"))
    )
    (net (code "97") (name "Net-(IC16-FB)") (class "Default")
      (node (ref "C100") (pin "2") (pinfunction "2_2") (pintype "passive"))
      (node (ref "IC16") (pin "2") (pinfunction "FB_2") (pintype "bidirectional"))
      (node (ref "R102") (pin "2") (pinfunction "2_2") (pintype "passive"))
      (node (ref "R43") (pin "1") (pinfunction "1_1") (pintype "passive"))
    )
    (net (code "98") (name "Net-(IC16-MODE)") (class "Default")
      (node (ref "IC16") (pin "10") (pinfunction "MODE_10") (pintype "bidirectional"))
      (node (ref "R101") (pin "2") (pinfunction "2_2") (pintype "passive"))
    )
    (net (code "99") (name "Net-(IC16-SS)") (class "Default")
      (node (ref "C104") (pin "1") (pinfunction "1_1") (pintype "passive"))
      (node (ref "IC16") (pin "5") (pinfunction "SS_5") (pintype "bidirectional"))
    )
    (net (code "100") (name "Net-(IC16-SW)") (class "Default")
      (node (ref "C96") (pin "1") (pinfunction "1_1") (pintype "passive"))
      (node (ref "IC16") (pin "6") (pinfunction "SW_6") (pintype "bidirectional"))
      (node (ref "L9") (pin "1") (pinfunction "1_1") (pintype "passive"))
    )
    (net (code "101") (name "Net-(L1-Pad2)") (class "Default")
      (node (ref "L1") (pin "2") (pinfunction "2_2") (pintype "passive"))
      (node (ref "R28") (pin "2") (pinfunction "2_2") (pintype "passive"))
      (node (ref "R6") (pin "1") (pinfunction "1_1") (pintype "passive"))
    )
    (net (code "102") (name "Net-(L2-Pad2)") (class "Default")
      (node (ref "L2") (pin "2") (pinfunction "2_2") (pintype "passive"))
      (node (ref "R53") (pin "1") (pinfunction "1_1") (pintype "passive"))
      (node (ref "R7") (pin "1") (pinfunction "1_1") (pintype "passive"))
    )
    (net (code "103") (name "Net-(LED1-PadC)") (class "Default")
      (node (ref "LED1") (pin "C") (pinfunction "C_C") (pintype "passive"))
      (node (ref "R58") (pin "2") (pinfunction "2_2") (pintype "passive"))
    )
    (net (code "104") (name "Net-(LED2-PadC)") (class "Default")
      (node (ref "LED2") (pin "C") (pinfunction "C_C") (pintype "passive"))
      (node (ref "R60") (pin "2") (pinfunction "2_2") (pintype "passive"))
    )
    (net (code "105") (name "Net-(LED3-PadC)") (class "Default")
      (node (ref "LED3") (pin "C") (pinfunction "C_C") (pintype "passive"))
      (node (ref "R80") (pin "2") (pinfunction "2_2") (pintype "passive"))
    )
    (net (code "106") (name "Net-(LED4-PadC)") (class "Default")
      (node (ref "LED4") (pin "C") (pinfunction "C_C") (pintype "passive"))
      (node (ref "R64") (pin "2") (pinfunction "2_2") (pintype "passive"))
    )
    (net (code "107") (name "Net-(LED5-PadC)") (class "Default")
      (node (ref "LED5") (pin "C") (pinfunction "C_C") (pintype "passive"))
      (node (ref "R72") (pin "2") (pinfunction "2_2") (pintype "passive"))
    )
    (net (code "108") (name "Net-(LED6-PadC)") (class "Default")
      (node (ref "LED6") (pin "C") (pinfunction "C_C") (pintype "passive"))
      (node (ref "R74") (pin "2") (pinfunction "2_2") (pintype "passive"))
    )
    (net (code "109") (name "Net-(LED7-PadC)") (class "Default")
      (node (ref "LED7") (pin "C") (pinfunction "C_C") (pintype "passive"))
      (node (ref "R76") (pin "2") (pinfunction "2_2") (pintype "passive"))
    )
    (net (code "110") (name "Net-(Q3-D-Pad5)") (class "Default")
      (node (ref "Q3") (pin "5") (pinfunction "D_5") (pintype "passive"))
      (node (ref "Q3") (pin "6") (pinfunction "D_6") (pintype "passive"))
      (node (ref "Q3") (pin "7") (pinfunction "D_7") (pintype "passive"))
      (node (ref "Q3") (pin "8") (pinfunction "D_8") (pintype "passive"))
      (node (ref "Q3") (pin "TH") (pinfunction "D_TH") (pintype "passive"))
      (node (ref "R2") (pin "2A") (pinfunction "2A_2A") (pintype "passive"))
    )
    (net (code "111") (name "Net-(Q5-D-Pad5)") (class "Default")
      (node (ref "Q5") (pin "5") (pinfunction "D_5") (pintype "passive"))
      (node (ref "Q5") (pin "6") (pinfunction "D_6") (pintype "passive"))
      (node (ref "Q5") (pin "7") (pinfunction "D_7") (pintype "passive"))
      (node (ref "Q5") (pin "8") (pinfunction "D_8") (pintype "passive"))
      (node (ref "Q5") (pin "TH") (pinfunction "D_TH") (pintype "passive"))
      (node (ref "R30") (pin "2A") (pinfunction "2A_2A") (pintype "passive"))
    )
    (net (code "112") (name "Net-(Q9A-D-Pad6)") (class "Default")
      (node (ref "Q9") (pin "6") (pinfunction "D_6") (pintype "passive"))
      (node (ref "Q9") (pin "7") (pinfunction "D_7") (pintype "passive"))
      (node (ref "R74") (pin "1") (pinfunction "1_1") (pintype "passive"))
    )
    (net (code "113") (name "Net-(Q9B-D-Pad3)") (class "Default")
      (node (ref "Q9") (pin "3") (pinfunction "D_3") (pintype "passive"))
      (node (ref "Q9") (pin "8") (pinfunction "D_8") (pintype "passive"))
      (node (ref "R76") (pin "1") (pinfunction "1_1") (pintype "passive"))
    )
    (net (code "114") (name "Net-(Q10A-D-Pad6)") (class "Default")
      (node (ref "Q10") (pin "6") (pinfunction "D_6") (pintype "passive"))
      (node (ref "Q10") (pin "7") (pinfunction "D_7") (pintype "passive"))
      (node (ref "R60") (pin "1") (pinfunction "1_1") (pintype "passive"))
    )
    (net (code "115") (name "Net-(Q10B-D-Pad3)") (class "Default")
      (node (ref "Q10") (pin "3") (pinfunction "D_3") (pintype "passive"))
      (node (ref "Q10") (pin "8") (pinfunction "D_8") (pintype "passive"))
      (node (ref "R64") (pin "1") (pinfunction "1_1") (pintype "passive"))
    )
    (net (code "116") (name "Net-(Q11A-D-Pad6)") (class "Default")
      (node (ref "Q11") (pin "6") (pinfunction "D_6") (pintype "passive"))
      (node (ref "Q11") (pin "7") (pinfunction "D_7") (pintype "passive"))
      (node (ref "R72") (pin "1") (pinfunction "1_1") (pintype "passive"))
    )
    (net (code "117") (name "Net-(Q11B-D-Pad3)") (class "Default")
      (node (ref "Q11") (pin "3") (pinfunction "D_3") (pintype "passive"))
      (node (ref "Q11") (pin "8") (pinfunction "D_8") (pintype "passive"))
      (node (ref "R58") (pin "1") (pinfunction "1_1") (pintype "passive"))
    )
    (net (code "118") (name "Net-(R2-Pad1B)") (class "Default")
      (node (ref "R2") (pin "1B") (pinfunction "1B_1B") (pintype "passive"))
      (node (ref "R45") (pin "2") (pinfunction "2_2") (pintype "passive"))
    )
    (net (code "119") (name "Net-(R24-Pad1)") (class "Default")
      (node (ref "R24") (pin "1") (pinfunction "1_1") (pintype "passive"))
      (node (ref "SJ4") (pin "1") (pinfunction "1_1") (pintype "passive"))
    )
    (net (code "120") (name "Net-(R25-Pad2)") (class "Default")
      (node (ref "R25") (pin "2") (pinfunction "2_2") (pintype "passive"))
      (node (ref "SJ3") (pin "1") (pinfunction "1_1") (pintype "passive"))
    )
    (net (code "121") (name "Net-(R26-Pad2)") (class "Default")
      (node (ref "R26") (pin "2") (pinfunction "2_2") (pintype "passive"))
      (node (ref "SJ2") (pin "1") (pinfunction "1_1") (pintype "passive"))
    )
    (net (code "122") (name "Net-(R30-Pad1B)") (class "Default")
      (node (ref "R30") (pin "1B") (pinfunction "1B_1B") (pintype "passive"))
      (node (ref "R50") (pin "2") (pinfunction "2_2") (pintype "passive"))
    )
    (net (code "123") (name "PG_AUX") (class "Default")
      (node (ref "IC14") (pin "4") (pinfunction "PG_4") (pintype "bidirectional"))
    )
    (net (code "124") (name "PG_AUX_1") (class "Default")
      (node (ref "IC1") (pin "8") (pinfunction "PGD_8") (pintype "output"))
      (node (ref "Q11") (pin "2") (pinfunction "G_2") (pintype "passive"))
      (node (ref "R71") (pin "1") (pinfunction "1_1") (pintype "passive"))
    )
    (net (code "125") (name "PG_AUX_2") (class "Default")
      (node (ref "IC6") (pin "8") (pinfunction "PGD_8") (pintype "output"))
      (node (ref "Q9") (pin "2") (pinfunction "G_2") (pintype "passive"))
      (node (ref "R73") (pin "1") (pinfunction "1_1") (pintype "passive"))
    )
    (net (code "126") (name "PG_AUX_3") (class "Default")
      (node (ref "IC10") (pin "8") (pinfunction "PGD_8") (pintype "output"))
      (node (ref "Q9") (pin "5") (pinfunction "G_5") (pintype "passive"))
      (node (ref "R75") (pin "1") (pinfunction "1_1") (pintype "passive"))
    )
    (net (code "127") (name "PG_DCDC1") (class "Default")
      (node (ref "IC7") (pin "4") (pinfunction "PG_4") (pintype "bidirectional"))
      (node (ref "Q10") (pin "2") (pinfunction "G_2") (pintype "passive"))
      (node (ref "R59") (pin "1") (pinfunction "1_1") (pintype "passive"))
    )
    (net (code "128") (name "PG_SERVO") (class "Default")
      (node (ref "IC16") (pin "4") (pinfunction "PG_4") (pintype "bidirectional"))
      (node (ref "Q10") (pin "5") (pinfunction "G_5") (pintype "passive"))
      (node (ref "R63") (pin "1") (pinfunction "1_1") (pintype "passive"))
    )
    (net (code "129") (name "VBAT") (class "Default")
      (node (ref "C14") (pin "2") (pinfunction "+_2") (pintype "passive"))
      (node (ref "C2") (pin "1") (pinfunction "1_1") (pintype "passive"))
      (node (ref "C26") (pin "1") (pinfunction "1_1") (pintype "passive"))
      (node (ref "C27") (pin "1") (pinfunction "1_1") (pintype "passive"))
      (node (ref "C28") (pin "1") (pinfunction "1_1") (pintype "passive"))
      (node (ref "C3") (pin "1") (pinfunction "1_1") (pintype "passive"))
      (node (ref "C4") (pin "1") (pinfunction "1_1") (pintype "passive"))
      (node (ref "C5") (pin "1") (pinfunction "1_1") (pintype "passive"))
      (node (ref "C53") (pin "1") (pinfunction "1_1") (pintype "passive"))
      (node (ref "C79") (pin "1") (pinfunction "1_1") (pintype "passive"))
      (node (ref "C80") (pin "1") (pinfunction "1_1") (pintype "passive"))
      (node (ref "C81") (pin "1") (pinfunction "1_1") (pintype "passive"))
      (node (ref "C97") (pin "1") (pinfunction "1_1") (pintype "passive"))
      (node (ref "C98") (pin "1") (pinfunction "1_1") (pintype "passive"))
      (node (ref "C99") (pin "1") (pinfunction "1_1") (pintype "passive"))
      (node (ref "IC14") (pin "8") (pinfunction "VIN_8") (pintype "bidirectional"))
      (node (ref "IC16") (pin "8") (pinfunction "VIN_8") (pintype "bidirectional"))
      (node (ref "IC2") (pin "20") (pinfunction "VBIAS_20") (pintype "bidirectional"))
      (node (ref "IC5") (pin "6") (pinfunction "IP-_6") (pintype "bidirectional"))
      (node (ref "IC7") (pin "8") (pinfunction "VIN_8") (pintype "bidirectional"))
      (node (ref "LED3") (pin "A") (pinfunction "A_A") (pintype "passive"))
      (node (ref "R100") (pin "2") (pinfunction "2_2") (pintype "passive"))
      (node (ref "R15") (pin "2") (pinfunction "2_2") (pintype "passive"))
      (node (ref "R27") (pin "2") (pinfunction "2_2") (pintype "passive"))
      (node (ref "R38") (pin "2") (pinfunction "2_2") (pintype "passive"))
      (node (ref "R56") (pin "1") (pinfunction "1_1") (pintype "passive"))
      (node (ref "R6") (pin "2") (pinfunction "2_2") (pintype "passive"))
      (node (ref "R7") (pin "2") (pinfunction "2_2") (pintype "passive"))
      (node (ref "R88") (pin "2") (pinfunction "2_2") (pintype "passive"))
      (node (ref "X3") (pin "POS") (pinfunction "1_POS") (pintype "passive"))
    )
    (net (code "130") (name "VBAT1") (class "Default")
      (node (ref "C35") (pin "1") (pinfunction "1_1") (pintype "passive"))
      (node (ref "IC8") (pin "2") (pinfunction "A_2") (pintype "bidirectional"))
      (node (ref "Q2") (pin "1") (pinfunction "S_1") (pintype "passive"))
      (node (ref "Q2") (pin "2") (pinfunction "S_2") (pintype "passive"))
      (node (ref "Q2") (pin "3") (pinfunction "S_3") (pintype "passive"))
      (node (ref "SW1") (pin "2") (pinfunction "2_2") (pintype "bidirectional"))
      (node (ref "X1") (pin "POS") (pinfunction "1_POS") (pintype "passive"))
    )
    (net (code "131") (name "VBAT2") (class "Default")
      (node (ref "C19") (pin "1") (pinfunction "1_1") (pintype "passive"))
      (node (ref "IC3") (pin "2") (pinfunction "A_2") (pintype "bidirectional"))
      (node (ref "Q4") (pin "1") (pinfunction "S_1") (pintype "passive"))
      (node (ref "Q4") (pin "2") (pinfunction "S_2") (pintype "passive"))
      (node (ref "Q4") (pin "3") (pinfunction "S_3") (pintype "passive"))
      (node (ref "SW1") (pin "5") (pinfunction "5_5") (pintype "bidirectional"))
      (node (ref "X2") (pin "POS") (pinfunction "1_POS") (pintype "passive"))
    )
    (net (code "132") (name "VBAT_SW") (class "Default")
      (node (ref "C65") (pin "1") (pinfunction "1_1") (pintype "passive"))
      (node (ref "IC11") (pin "6") (pinfunction "IN_6") (pintype "bidirectional"))
      (node (ref "IC3") (pin "15") (pinfunction "OUT_15") (pintype "bidirectional"))
      (node (ref "IC3") (pin "16") (pinfunction "SLEEP_OV_16") (pintype "bidirectional"))
      (node (ref "IC5") (pin "5") (pinfunction "IP+_5") (pintype "bidirectional"))
      (node (ref "IC8") (pin "15") (pinfunction "OUT_15") (pintype "bidirectional"))
      (node (ref "IC8") (pin "16") (pinfunction "SLEEP_OV_16") (pintype "bidirectional"))
      (node (ref "Q3") (pin "1") (pinfunction "S_1") (pintype "passive"))
      (node (ref "Q3") (pin "2") (pinfunction "S_2") (pintype "passive"))
      (node (ref "Q3") (pin "3") (pinfunction "S_3") (pintype "passive"))
      (node (ref "Q5") (pin "1") (pinfunction "S_1") (pintype "passive"))
      (node (ref "Q5") (pin "2") (pinfunction "S_2") (pintype "passive"))
      (node (ref "Q5") (pin "3") (pinfunction "S_3") (pintype "passive"))
      (node (ref "R61") (pin "2") (pinfunction "2_2") (pintype "passive"))
      (node (ref "R78") (pin "2") (pinfunction "2_2") (pintype "passive"))
    )
    (net (code "133") (name "VCC_5V_AUX") (class "Default")
      (node (ref "C1") (pin "1") (pinfunction "1_1") (pintype "passive"))
      (node (ref "C61") (pin "1") (pinfunction "1_1") (pintype "passive"))
      (node (ref "C63") (pin "1") (pinfunction "1_1") (pintype "passive"))
      (node (ref "C83") (pin "1") (pinfunction "1_1") (pintype "passive"))
      (node (ref "C84") (pin "1") (pinfunction "1_1") (pintype "passive"))
      (node (ref "C85") (pin "1") (pinfunction "1_1") (pintype "passive"))
      (node (ref "IC1") (pin "1") (pinfunction "VIN_1") (pintype "power_in"))
      (node (ref "IC1") (pin "2") (pinfunction "VIN_2") (pintype "power_in"))
      (node (ref "IC10") (pin "1") (pinfunction "VIN_1") (pintype "power_in"))
      (node (ref "IC10") (pin "2") (pinfunction "VIN_2") (pintype "power_in"))
      (node (ref "IC6") (pin "1") (pinfunction "VIN_1") (pintype "power_in"))
      (node (ref "IC6") (pin "2") (pinfunction "VIN_2") (pintype "power_in"))
      (node (ref "L7") (pin "2") (pinfunction "2_2") (pintype "passive"))
      (node (ref "R1") (pin "2") (pinfunction "2_2") (pintype "passive"))
      (node (ref "R3") (pin "2") (pinfunction "2_2") (pintype "passive"))
      (node (ref "R68") (pin "2") (pinfunction "2_2") (pintype "passive"))
      (node (ref "R92") (pin "2") (pinfunction "2_2") (pintype "passive"))
      (node (ref "SJ1") (pin "1") (pinfunction "1_1") (pintype "passive"))
      (node (ref "SJ6") (pin "2") (pinfunction "2_2") (pintype "passive"))
      (node (ref "SJ7") (pin "2") (pinfunction "2_2") (pintype "passive"))
      (node (ref "SJ8") (pin "2") (pinfunction "2_2") (pintype "passive"))
    )
    (net (code "134") (name "VCC_5V_RPI") (class "Default")
      (node (ref "C31") (pin "1") (pinfunction "1_1") (pintype "passive"))
      (node (ref "C32") (pin "1") (pinfunction "1_1") (pintype "passive"))
      (node (ref "C33") (pin "1") (pinfunction "1_1") (pintype "passive"))
      (node (ref "L3") (pin "2") (pinfunction "2_2") (pintype "passive"))
      (node (ref "R42") (pin "2") (pinfunction "2_2") (pintype "passive"))
      (node (ref "X14") (pin "1") (pinfunction "1_1") (pintype "passive"))
      (node (ref "X14") (pin "2") (pinfunction "1_2") (pintype "passive"))
    )
    (net (code "135") (name "VCC_6V_SERVO") (class "Default")
      (node (ref "C101") (pin "1") (pinfunction "1_1") (pintype "passive"))
      (node (ref "C102") (pin "1") (pinfunction "1_1") (pintype "passive"))
      (node (ref "C103") (pin "1") (pinfunction "1_1") (pintype "passive"))
      (node (ref "L9") (pin "2") (pinfunction "2_2") (pintype "passive"))
      (node (ref "R104") (pin "2") (pinfunction "2_2") (pintype "passive"))
      (node (ref "X16") (pin "1") (pinfunction "1_1") (pintype "passive"))
      (node (ref "X16") (pin "2") (pinfunction "1_2") (pintype "passive"))
    )
    (net (code "136") (name "VOLTAGE_SENSE") (class "Default")
      (node (ref "R79") (pin "2") (pinfunction "2_2") (pintype "passive"))
      (node (ref "X4") (pin "1") (pinfunction "1_1") (pintype "passive"))
      (node (ref "X4") (pin "2") (pinfunction "1_2") (pintype "passive"))
    )
    (net (code "137") (name "VS") (class "Default")
      (node (ref "C67") (pin "1") (pinfunction "1_1") (pintype "passive"))
      (node (ref "IC12") (pin "1") (pinfunction "+IN_1") (pintype "input"))
      (node (ref "R61") (pin "1") (pinfunction "1_1") (pintype "passive"))
      (node (ref "R62") (pin "2") (pinfunction "2_2") (pintype "passive"))
    )
    (net (code "138") (name "unconnected-(IC1-OVP-Pad7)") (class "Default")
      (node (ref "IC1") (pin "7") (pinfunction "OVP_7") (pintype "input"))
    )
    (net (code "139") (name "unconnected-(IC2-CLKOUT-Pad3)") (class "Default")
      (node (ref "IC2") (pin "3") (pinfunction "CLKOUT_3") (pintype "bidirectional"))
    )
    (net (code "140") (name "unconnected-(IC2-NC-Pad12)") (class "Default")
      (node (ref "IC2") (pin "12") (pinfunction "NC_12") (pintype "bidirectional"))
    )
    (net (code "141") (name "unconnected-(IC3-NC-Pad8)") (class "Default")
      (node (ref "IC3") (pin "8") (pinfunction "NC_8") (pintype "bidirectional"))
    )
    (net (code "142") (name "unconnected-(IC3-NC-Pad17)") (class "Default")
      (node (ref "IC3") (pin "17") (pinfunction "NC_17") (pintype "bidirectional"))
    )
    (net (code "143") (name "unconnected-(IC3-NC-Pad21)") (class "Default")
      (node (ref "IC3") (pin "21") (pinfunction "NC_21") (pintype "bidirectional"))
    )
    (net (code "144") (name "unconnected-(IC3-RTN-PadPAD)") (class "Default")
      (node (ref "IC3") (pin "PAD") (pinfunction "RTN_PAD") (pintype "bidirectional"))
    )
    (net (code "145") (name "unconnected-(IC6-OVP-Pad7)") (class "Default")
      (node (ref "IC6") (pin "7") (pinfunction "OVP_7") (pintype "input"))
    )
    (net (code "146") (name "unconnected-(IC8-NC-Pad8)") (class "Default")
      (node (ref "IC8") (pin "8") (pinfunction "NC_8") (pintype "bidirectional"))
    )
    (net (code "147") (name "unconnected-(IC8-NC-Pad17)") (class "Default")
      (node (ref "IC8") (pin "17") (pinfunction "NC_17") (pintype "bidirectional"))
    )
    (net (code "148") (name "unconnected-(IC8-NC-Pad21)") (class "Default")
      (node (ref "IC8") (pin "21") (pinfunction "NC_21") (pintype "bidirectional"))
    )
    (net (code "149") (name "unconnected-(IC8-RTN-PadPAD)") (class "Default")
      (node (ref "IC8") (pin "PAD") (pinfunction "RTN_PAD") (pintype "bidirectional"))
    )
    (net (code "150") (name "unconnected-(IC10-OVP-Pad7)") (class "Default")
      (node (ref "IC10") (pin "7") (pinfunction "OVP_7") (pintype "input"))
    )
    (net (code "151") (name "unconnected-(IC11-NC-Pad2)") (class "Default")
      (node (ref "IC11") (pin "2") (pinfunction "NC_2") (pintype "bidirectional"))
    )
    (net (code "152") (name "unconnected-(IC11-NC-Pad5)") (class "Default")
      (node (ref "IC11") (pin "5") (pinfunction "NC_5") (pintype "bidirectional"))
    )
  )
)
